# Pack_Supervisor_97x127mm_Rev_B.net
KiCad netlist of a schematic drawn in EAGLE
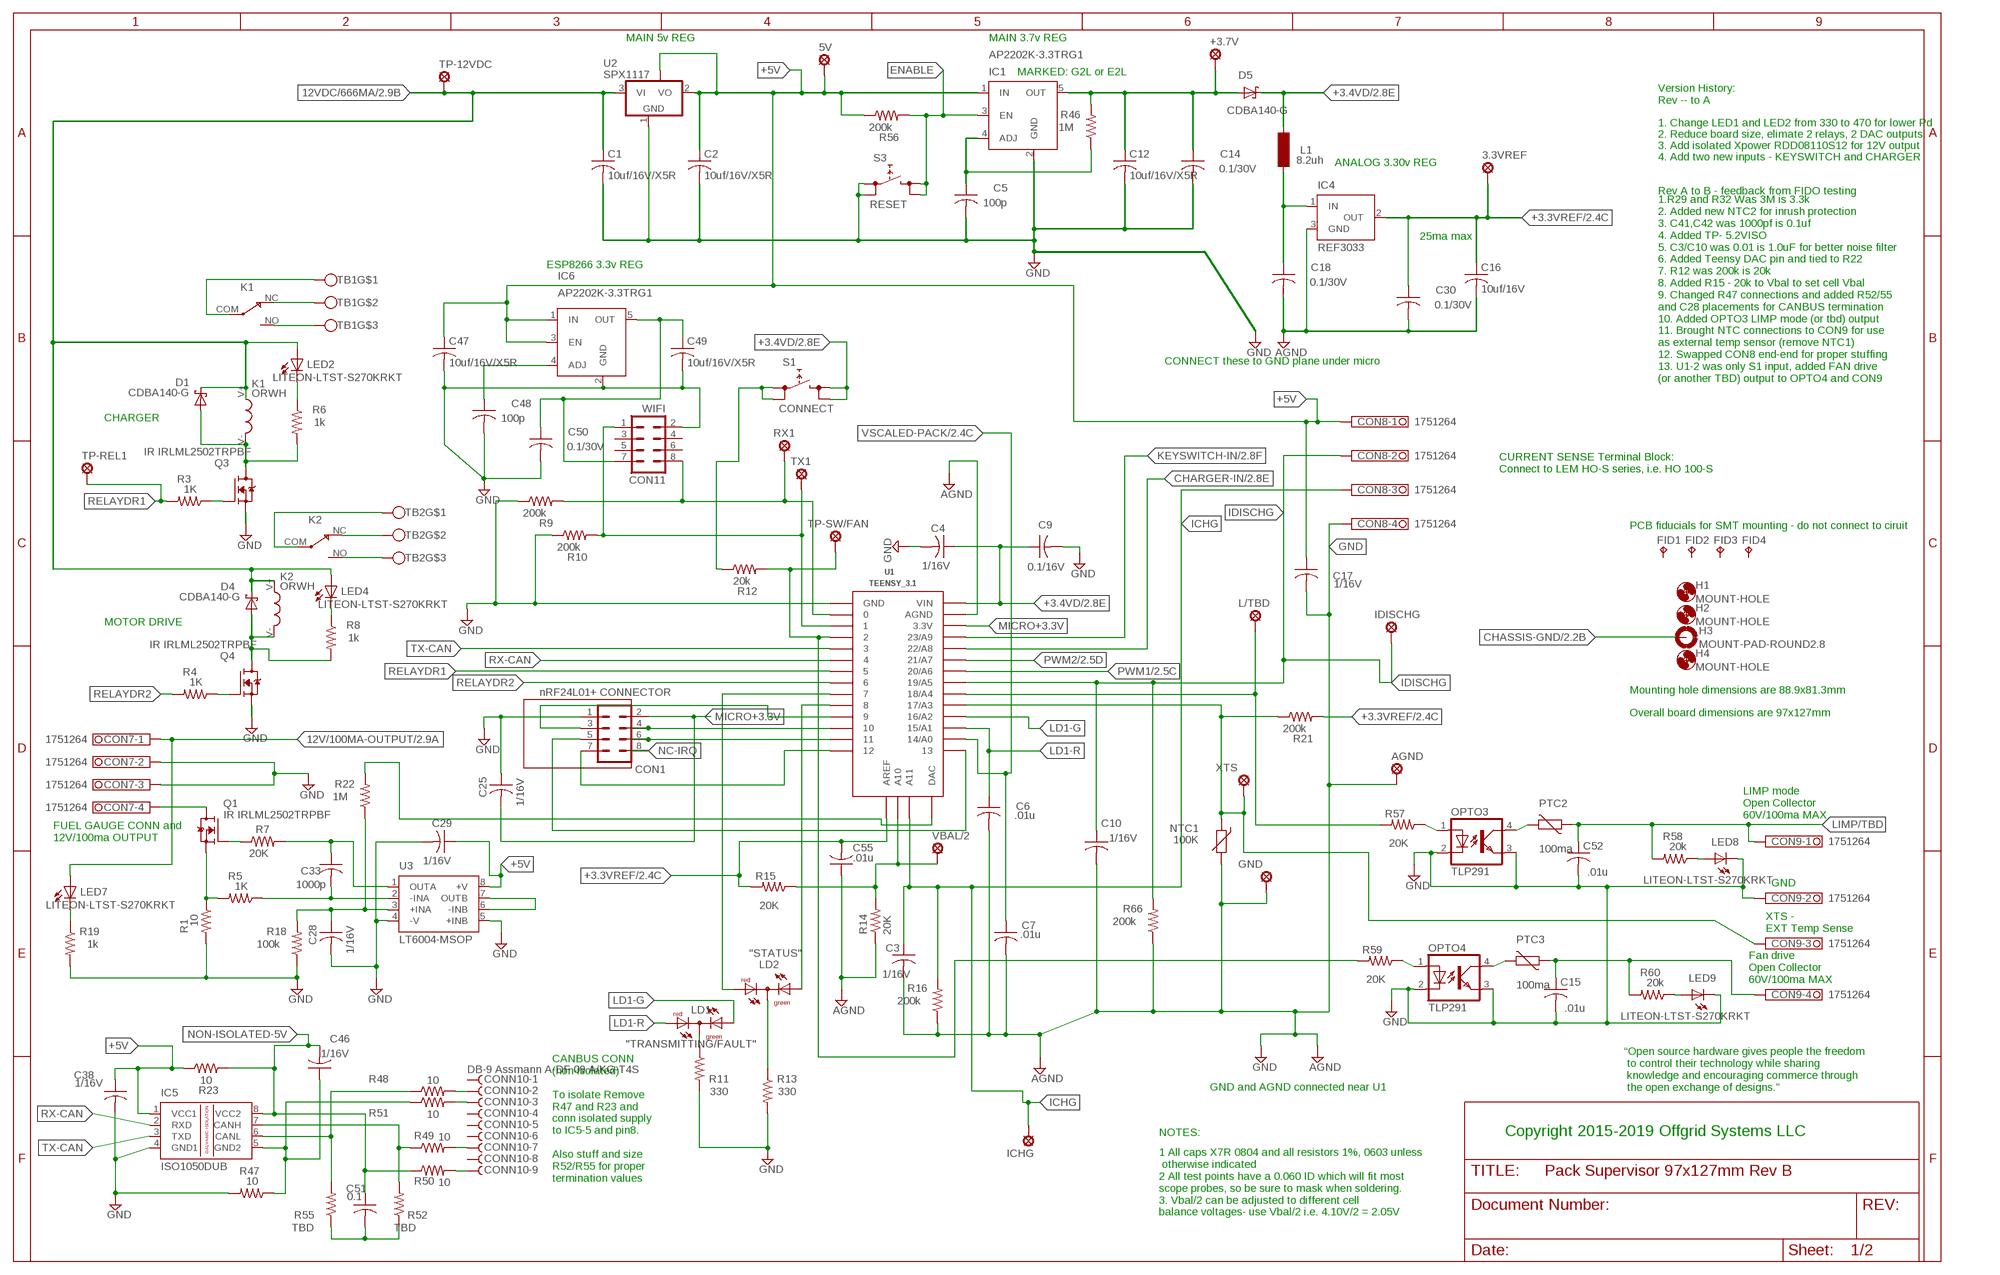
[diagram p0: schematic, sheet 1]
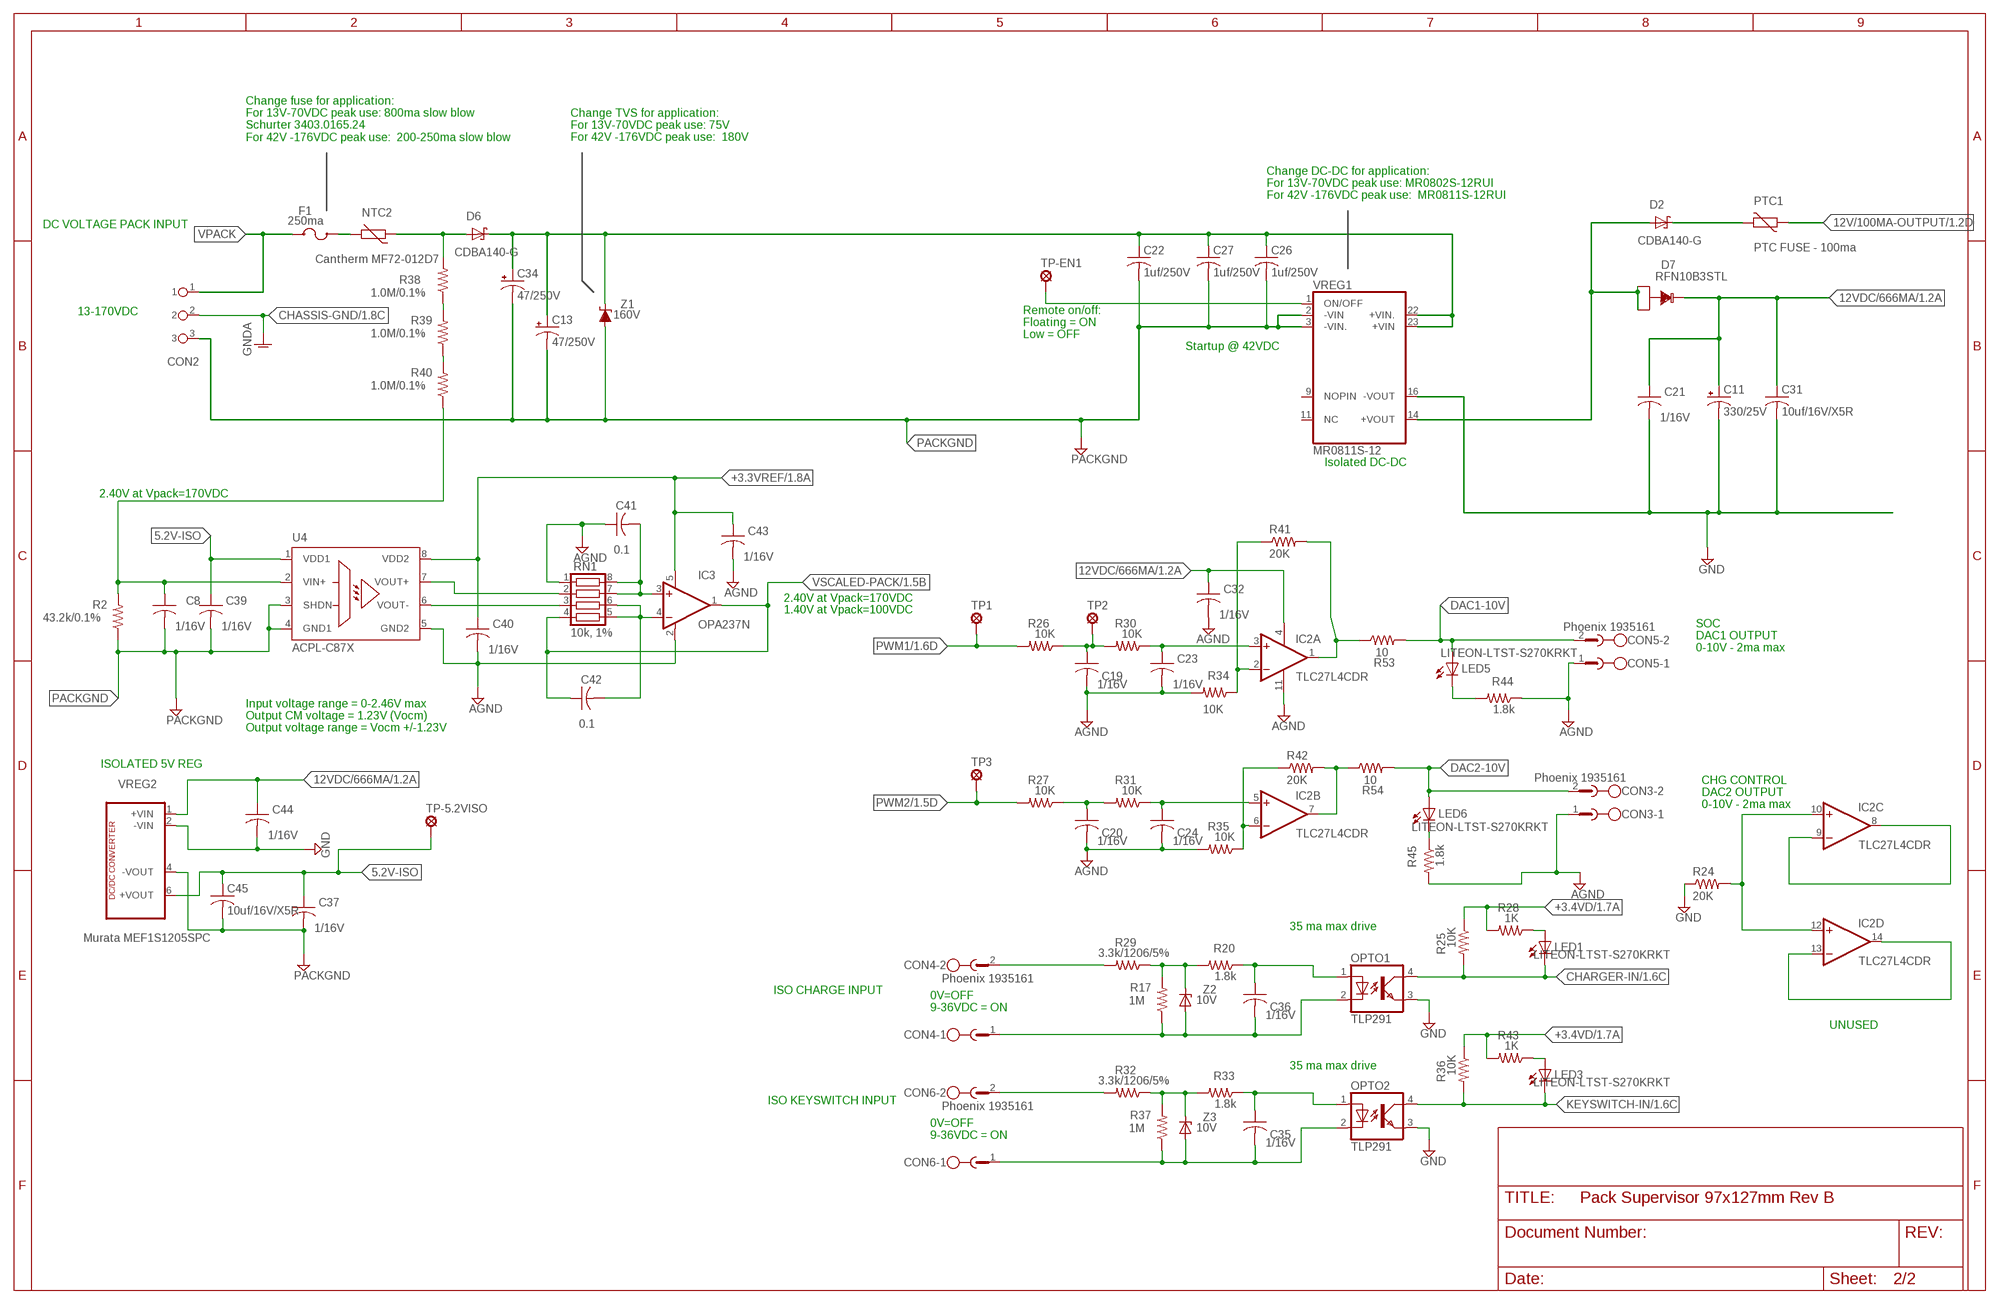
[diagram p1: schematic, sheet 2]

(export (version "E")
  (design (tool "Eeschema 10.0.6"))
  (components
    (comp (ref "+3.7V")
      (value "LSP10")
      (footprint "eagle-import:LSP10")
      (libsource (lib "eagle-import") (part "LSP10"))
    )
    (comp (ref "3.3VREF")
      (value "LSP10")
      (footprint "eagle-import:LSP10")
      (libsource (lib "eagle-import") (part "LSP10"))
    )
    (comp (ref "5V")
      (value "LSP10")
      (footprint "eagle-import:LSP10")
      (libsource (lib "eagle-import") (part "LSP10"))
    )
    (comp (ref "AGND")
      (value "LSP10")
      (footprint "eagle-import:LSP10")
      (libsource (lib "eagle-import") (part "LSP10"))
    )
    (comp (ref "C1")
      (value "10uf/16V/X5R")
      (footprint "eagle-import:C0805K")
      (fields (field (name "MPN") "Murata GRM21BR61C106ME15L"))
      (libsource (lib "eagle-import") (part "C-USC0805K"))
    )
    (comp (ref "C2")
      (value "10uf/16V/X5R")
      (footprint "eagle-import:C0805K")
      (fields (field (name "MPN") "Murata GRM21BR61C106ME15L"))
      (libsource (lib "eagle-import") (part "C-USC0805K"))
    )
    (comp (ref "C3")
      (value "1/16V")
      (footprint "eagle-import:TIMS_INDUCTOR_C0805")
      (fields (field (name "MPN") "Kemet C0805C103K5RACTU"))
      (libsource (lib "eagle-import") (part "TIMS_INDUCTOR_C-USC0805"))
    )
    (comp (ref "C4")
      (value "1/16V")
      (footprint "eagle-import:TIMS_INDUCTOR_C0805")
      (fields (field (name "MPN") "Kemet C0805C105K4RACTU"))
      (libsource (lib "eagle-import") (part "TIMS_INDUCTOR_C-USC0805"))
    )
    (comp (ref "C5")
      (value "100p")
      (footprint "eagle-import:TIMS_INDUCTOR_C0805")
      (fields (field (name "MPN") "Kemet C0805C104K5RACTU"))
      (libsource (lib "eagle-import") (part "TIMS_INDUCTOR_C-USC0805"))
    )
    (comp (ref "C6")
      (value ".01u")
      (footprint "eagle-import:TIMS_INDUCTOR_C0805")
      (fields (field (name "MPN") "Kemet C0805C103K5RACTU"))
      (libsource (lib "eagle-import") (part "TIMS_INDUCTOR_C-USC0805"))
    )
    (comp (ref "C7")
      (value ".01u")
      (footprint "eagle-import:TIMS_INDUCTOR_C0805")
      (fields (field (name "MPN") "Kemet C0805C103K5RACTU"))
      (libsource (lib "eagle-import") (part "TIMS_INDUCTOR_C-USC0805"))
    )
    (comp (ref "C9")
      (value "0.1/16V")
      (footprint "eagle-import:TIMS_INDUCTOR_C0805")
      (fields (field (name "MPN") "Kemet C0805C104K5RACTU"))
      (libsource (lib "eagle-import") (part "TIMS_INDUCTOR_C-USC0805"))
    )
    (comp (ref "C10")
      (value "1/16V")
      (footprint "eagle-import:TIMS_INDUCTOR_C0805")
      (fields (field (name "MPN") "Kemet C0805C103K5RACTU"))
      (libsource (lib "eagle-import") (part "TIMS_INDUCTOR_C-USC0805"))
    )
    (comp (ref "C12")
      (value "10uf/16V/X5R")
      (footprint "eagle-import:C0805K")
      (fields (field (name "MPN") "Murata GRM21BR61C106ME15L"))
      (libsource (lib "eagle-import") (part "C-USC0805K"))
    )
    (comp (ref "C14")
      (value "0.1/30V")
      (footprint "eagle-import:TIMS_INDUCTOR_C0805")
      (fields (field (name "MPN") "Kemet C0805C104K5RACTU"))
      (libsource (lib "eagle-import") (part "TIMS_INDUCTOR_C-USC0805"))
    )
    (comp (ref "C15")
      (value ".01u")
      (footprint "eagle-import:TIMS_INDUCTOR_C0805")
      (fields (field (name "MPN") "Kemet C0805C103K5RACTU"))
      (libsource (lib "eagle-import") (part "TIMS_INDUCTOR_C-USC0805"))
    )
    (comp (ref "C16")
      (value "10uf/16V")
      (footprint "eagle-import:C0805K")
      (fields (field (name "MPN") "Murata GRM21BR61A476ME15L"))
      (libsource (lib "eagle-import") (part "C-USC0805K"))
    )
    (comp (ref "C17")
      (value "1/16V")
      (footprint "eagle-import:TIMS_INDUCTOR_C0805")
      (fields (field (name "MPN") "Kemet C0805C105K4RACTU"))
      (libsource (lib "eagle-import") (part "TIMS_INDUCTOR_C-USC0805"))
    )
    (comp (ref "C18")
      (value "0.1/30V")
      (footprint "eagle-import:TIMS_INDUCTOR_C0805")
      (fields (field (name "MPN") "Kemet C0805C104K5RACTU"))
      (libsource (lib "eagle-import") (part "TIMS_INDUCTOR_C-USC0805"))
    )
    (comp (ref "C25")
      (value "1/16V")
      (footprint "eagle-import:TIMS_INDUCTOR_C0805")
      (fields (field (name "MPN") "Kemet C0805C105K4RACTU"))
      (libsource (lib "eagle-import") (part "TIMS_INDUCTOR_C-USC0805"))
    )
    (comp (ref "C28")
      (value "1/16V")
      (footprint "eagle-import:TIMS_INDUCTOR_C0805")
      (fields (field (name "MPN") "Kemet C0805C105K4RACTU"))
      (libsource (lib "eagle-import") (part "TIMS_INDUCTOR_C-USC0805"))
    )
    (comp (ref "C29")
      (value "1/16V")
      (footprint "eagle-import:TIMS_INDUCTOR_C0805")
      (fields (field (name "MPN") "Kemet C0805C105K4RACTU"))
      (libsource (lib "eagle-import") (part "TIMS_INDUCTOR_C-USC0805"))
    )
    (comp (ref "C30")
      (value "0.1/30V")
      (footprint "eagle-import:TIMS_INDUCTOR_C0805")
      (fields (field (name "MPN") "Kemet C0805C104K5RACTU"))
      (libsource (lib "eagle-import") (part "TIMS_INDUCTOR_C-USC0805"))
    )
    (comp (ref "C33")
      (value "1000p")
      (footprint "eagle-import:TIMS_INDUCTOR_C0805")
      (fields (field (name "MPN") "Kemet C0805C105K4RACTU"))
      (libsource (lib "eagle-import") (part "TIMS_INDUCTOR_C-USC0805"))
    )
    (comp (ref "C38")
      (value "1/16V")
      (footprint "eagle-import:TIMS_INDUCTOR_C0805")
      (fields (field (name "MPN") "Kemet C0805C105K4RACTU"))
      (libsource (lib "eagle-import") (part "TIMS_INDUCTOR_C-USC0805"))
    )
    (comp (ref "C46")
      (value "1/16V")
      (footprint "eagle-import:TIMS_INDUCTOR_C0805")
      (fields (field (name "MPN") "Kemet C0805C105K4RACTU"))
      (libsource (lib "eagle-import") (part "TIMS_INDUCTOR_C-USC0805"))
    )
    (comp (ref "C47")
      (value "10uf/16V/X5R")
      (footprint "eagle-import:C0805K")
      (fields (field (name "MPN") "Murata GRM21BR61C106ME15L"))
      (libsource (lib "eagle-import") (part "C-USC0805K"))
    )
    (comp (ref "C48")
      (value "100p")
      (footprint "eagle-import:TIMS_INDUCTOR_C0805")
      (fields (field (name "MPN") "Kemet C0805C104K5RACTU"))
      (libsource (lib "eagle-import") (part "TIMS_INDUCTOR_C-USC0805"))
    )
    (comp (ref "C49")
      (value "10uf/16V/X5R")
      (footprint "eagle-import:C0805K")
      (fields (field (name "MPN") "Murata GRM21BR61C106ME15L"))
      (libsource (lib "eagle-import") (part "C-USC0805K"))
    )
    (comp (ref "C50")
      (value "0.1/30V")
      (footprint "eagle-import:TIMS_INDUCTOR_C0805")
      (fields (field (name "MPN") "Kemet C0805C104K5RACTU"))
      (libsource (lib "eagle-import") (part "TIMS_INDUCTOR_C-USC0805"))
    )
    (comp (ref "C51")
      (value "0.1")
      (footprint "eagle-import:TIMS_INDUCTOR_C0805")
      (fields (field (name "MPN") "Kemet C0805C105K4RACTU"))
      (libsource (lib "eagle-import") (part "TIMS_INDUCTOR_C-USC0805"))
    )
    (comp (ref "C52")
      (value ".01u")
      (footprint "eagle-import:TIMS_INDUCTOR_C0805")
      (fields (field (name "MPN") "Kemet C0805C103K5RACTU"))
      (libsource (lib "eagle-import") (part "TIMS_INDUCTOR_C-USC0805"))
    )
    (comp (ref "C55")
      (value ".01u")
      (footprint "eagle-import:C0805")
      (fields (field (name "MPN") "Welwyn PCF0603R-3K01BT1"))
      (libsource (lib "eagle-import") (part "C-USC0805"))
    )
    (comp (ref "CON1")
      (value "nRF24L01+ CONNECTOR")
      (footprint "eagle-import:NRF24L01")
      (libsource (lib "eagle-import") (part "NRF24L01"))
    )
    (comp (ref "CON7")
      (value "1751264")
      (footprint "eagle-import:1751264")
      (libsource (lib "eagle-import") (part "1751264"))
    )
    (comp (ref "CON8")
      (value "1751264")
      (footprint "eagle-import:1751264")
      (libsource (lib "eagle-import") (part "1751264"))
    )
    (comp (ref "CON9")
      (value "1751264")
      (footprint "eagle-import:1751264")
      (libsource (lib "eagle-import") (part "1751264"))
    )
    (comp (ref "CON11")
      (value "WIFI")
      (footprint "eagle-import:MA04-2")
      (fields (field (name "MPN") "Sullins PPPC042LFBN-RC"))
      (libsource (lib "eagle-import") (part "MA04-2"))
    )
    (comp (ref "CONN10")
      (value "DB-9 Assmann A-DF 09 A/KG-T4S")
      (footprint "eagle-import:H5M09RA")
      (fields
        (field (name "100PCPRICE") ".563")
        (field (name "10PCPRICE") ".735")
        (field (name "MPN") "ASSMANN A-DS 09 A/KG-T4S")
      )
      (libsource (lib "eagle-import") (part "D-SUB9-H5M09RA"))
    )
    (comp (ref "D1")
      (value "CDBA140-G")
      (footprint "eagle-import:DO214AC")
      (fields (field (name "MPN") "comchip CDBA140-G"))
      (libsource (lib "eagle-import") (part "CDBA140-G"))
    )
    (comp (ref "D4")
      (value "CDBA140-G")
      (footprint "eagle-import:DO214AC")
      (fields (field (name "MPN") "comchip CDBA140-G"))
      (libsource (lib "eagle-import") (part "CDBA140-G"))
    )
    (comp (ref "D5")
      (value "CDBA140-G")
      (footprint "eagle-import:DO214AC")
      (fields (field (name "MPN") "comchip CDBA140-G"))
      (libsource (lib "eagle-import") (part "CDBA140-G"))
    )
    (comp (ref "FID1")
      (value "FIDUCIALTP10R")
      (footprint "eagle-import:TP10R")
      (libsource (lib "eagle-import") (part "FIDUCIALTP10R"))
    )
    (comp (ref "FID2")
      (value "FIDUCIALTP10R")
      (footprint "eagle-import:TP10R")
      (libsource (lib "eagle-import") (part "FIDUCIALTP10R"))
    )
    (comp (ref "FID3")
      (value "FIDUCIALTP10R")
      (footprint "eagle-import:TP10R")
      (libsource (lib "eagle-import") (part "FIDUCIALTP10R"))
    )
    (comp (ref "FID4")
      (value "FIDUCIALTP10R")
      (footprint "eagle-import:TP10R")
      (libsource (lib "eagle-import") (part "FIDUCIALTP10R"))
    )
    (comp (ref "GND")
      (value "LSP10")
      (footprint "eagle-import:LSP10")
      (libsource (lib "eagle-import") (part "LSP10"))
    )
    (comp (ref "H1")
      (value "MOUNT-HOLE")
      (footprint "eagle-import:2,6")
      (fields (field (name "MPN") "Keystone 9056"))
      (libsource (lib "eagle-import") (part "MOUNT-HOLE"))
    )
    (comp (ref "H2")
      (value "MOUNT-HOLE")
      (footprint "eagle-import:2,6")
      (libsource (lib "eagle-import") (part "MOUNT-HOLE"))
    )
    (comp (ref "H3")
      (value "MOUNT-PAD-ROUND2.8")
      (footprint "eagle-import:2,8-PAD")
      (libsource (lib "eagle-import") (part "MOUNT-PAD-ROUND2.8"))
    )
    (comp (ref "H4")
      (value "MOUNT-HOLE")
      (footprint "eagle-import:2,6")
      (libsource (lib "eagle-import") (part "MOUNT-HOLE"))
    )
    (comp (ref "IC1")
      (value "AP2202K-3.3TRG1")
      (footprint "eagle-import:SOT23-5")
      (fields
        (field (name "MF") "ALTERA CORPORATION")
        (field (name "MPN") "MIC5219BM5 TR")
        (field (name "MF_1") "Diodes INc")
        (field (name "MPN_1") "Diodes AP2202K-3.3TRG1")
      )
      (libsource (lib "eagle-import") (part "MIC5205"))
    )
    (comp (ref "IC4")
      (value "REF3033")
      (footprint "eagle-import:SOT23")
      (fields
        (field (name "MF") "MAXIM")
        (field (name "MPN") "MAX6520EUR-T")
        (field (name "MPN_1") "TI REF3033AIDBZR")
      )
      (libsource (lib "eagle-import") (part "MAX6520"))
    )
    (comp (ref "IC5")
      (value "ISO1050DUB")
      (footprint "eagle-import:DUB-R-PDSO-G8")
      (fields (field (name "MPN") "ISO1050DUBR") (field (name "MPN_1") "TI ISO1050DUBR"))
      (libsource (lib "eagle-import") (part "ISO1050DUB"))
    )
    (comp (ref "IC6")
      (value "AP2202K-3.3TRG1")
      (footprint "eagle-import:SOT23-5")
      (fields
        (field (name "MF") "ALTERA CORPORATION")
        (field (name "MPN") "MIC5219BM5 TR")
        (field (name "MF_1") "Diodes INc")
        (field (name "MPN_1") "Diodes AP2202K-3.3TRG1")
      )
      (libsource (lib "eagle-import") (part "MIC5205"))
    )
    (comp (ref "ICHG")
      (value "LSP10")
      (footprint "eagle-import:LSP10")
      (libsource (lib "eagle-import") (part "LSP10"))
    )
    (comp (ref "IDISCHG")
      (value "LSP10")
      (footprint "eagle-import:LSP10")
      (libsource (lib "eagle-import") (part "LSP10"))
    )
    (comp (ref "K1")
      (value "ORWH")
      (footprint "eagle-import:ORWH")
      (fields
        (field (name "MPN") "TE 1461069-5")
        (field (name "100PCPRICE") ".653")
        (field (name "1KPRICE") ".604")
      )
      (libsource (lib "eagle-import") (part "ORWH"))
    )
    (comp (ref "K2")
      (value "ORWH")
      (footprint "eagle-import:ORWH")
      (fields
        (field (name "MPN") "TE 1461069-5")
        (field (name "100PCPRICE") ".653")
        (field (name "1KPRICE") ".604")
      )
      (libsource (lib "eagle-import") (part "ORWH"))
    )
    (comp (ref "L/TBD")
      (value "LSP10")
      (footprint "eagle-import:LSP10")
      (libsource (lib "eagle-import") (part "LSP10"))
    )
    (comp (ref "L1")
      (value "8.2uh")
      (footprint "eagle-import:SM-1206")
      (fields (field (name "MPN") "Abracon AIML-1206-8R2K-T"))
      (libsource (lib "eagle-import") (part "SM-1206"))
    )
    (comp (ref "LD1")
      (value "\"TRANSMITTING/FAULT\"")
      (footprint "eagle-import:DUOLED-C-5MM")
      (fields (field (name "MPN") "Kingbright WP59EGC"))
      (libsource (lib "eagle-import") (part "DUOLED-RG-C"))
    )
    (comp (ref "LD2")
      (value "\"STATUS\"")
      (footprint "eagle-import:DUOLED-C-5MM")
      (fields (field (name "MPN") "Kingbright WP59EGC"))
      (libsource (lib "eagle-import") (part "DUOLED-RG-C"))
    )
    (comp (ref "LED2")
      (value "LITEON-LTST-S270KRKT")
      (footprint "eagle-import:LITEON-LTST-S270KRKT")
      (fields (field (name "MPN") "LiteOn LTST-S270KSKT "))
      (libsource (lib "eagle-import") (part "LITEON-LTST-S270KRKT"))
    )
    (comp (ref "LED4")
      (value "LITEON-LTST-S270KRKT")
      (footprint "eagle-import:LITEON-LTST-S270KRKT")
      (fields (field (name "MPN") "LiteOn LTST-S270KSKT "))
      (libsource (lib "eagle-import") (part "LITEON-LTST-S270KRKT"))
    )
    (comp (ref "LED7")
      (value "LITEON-LTST-S270KRKT")
      (footprint "eagle-import:LITEON-LTST-S270KRKT")
      (fields (field (name "MPN") "LiteOn LTST-S270KSKT "))
      (libsource (lib "eagle-import") (part "LITEON-LTST-S270KRKT"))
    )
    (comp (ref "LED8")
      (value "LITEON-LTST-S270KRKT")
      (footprint "eagle-import:LITEON-LTST-S270KRKT")
      (fields (field (name "MPN") "LiteOn LTST-S270KSKT "))
      (libsource (lib "eagle-import") (part "LITEON-LTST-S270KRKT"))
    )
    (comp (ref "LED9")
      (value "LITEON-LTST-S270KRKT")
      (footprint "eagle-import:LITEON-LTST-S270KRKT")
      (fields (field (name "MPN") "LiteOn LTST-S270KSKT "))
      (libsource (lib "eagle-import") (part "LITEON-LTST-S270KRKT"))
    )
    (comp (ref "NTC1")
      (value "100K")
      (footprint "eagle-import:0603")
      (fields (field (name "MPN") "MURATA NCP18WF104J03RB"))
      (libsource (lib "eagle-import") (part "NTC-MURATA-NCP18WF104J03RB"))
    )
    (comp (ref "OPTO3")
      (value "TLP291")
      (footprint "eagle-import:MINI-FLAT-4")
      (libsource (lib "eagle-import") (part "TLP283"))
    )
    (comp (ref "OPTO4")
      (value "TLP291")
      (footprint "eagle-import:MINI-FLAT-4")
      (libsource (lib "eagle-import") (part "TLP283"))
    )
    (comp (ref "PTC2")
      (value "100ma")
      (footprint "eagle-import:CT_CN0603")
      (fields (field (name "MPN") "Bel Fuse 0ZCM0010FF2G"))
      (libsource (lib "eagle-import") (part "VARISTORCN0603"))
    )
    (comp (ref "PTC3")
      (value "100ma")
      (footprint "eagle-import:CT_CN0603")
      (fields (field (name "MPN") "Bel Fuse 0ZCM0010FF2G"))
      (libsource (lib "eagle-import") (part "VARISTORCN0603"))
    )
    (comp (ref "Q1")
      (value "IRLML2502TRPBF")
      (footprint "eagle-import:SOT23")
      (fields (field (name "MPN") "IR IRLML2502TRPBF"))
      (libsource (lib "eagle-import") (part "IRLML2060TRPBF"))
    )
    (comp (ref "Q3")
      (value "IRLML2502TRPBF")
      (footprint "eagle-import:SOT23")
      (fields (field (name "MPN") "IR IRLML2502TRPBF"))
      (libsource (lib "eagle-import") (part "IRLML2060TRPBF"))
    )
    (comp (ref "Q4")
      (value "IRLML2502TRPBF")
      (footprint "eagle-import:SOT23")
      (fields (field (name "MPN") "IR IRLML2502TRPBF"))
      (libsource (lib "eagle-import") (part "IRLML2060TRPBF"))
    )
    (comp (ref "R1")
      (value "10")
      (footprint "eagle-import:R0603")
      (fields (field (name "MPN") "Bourns CR0603-FX-10R0ELF"))
      (libsource (lib "eagle-import") (part "rcl_R-US_R0603"))
    )
    (comp (ref "R3")
      (value "1K")
      (footprint "eagle-import:R0603")
      (fields (field (name "MPN") "Bourns CR0603-FX-1001ELF"))
      (libsource (lib "eagle-import") (part "rcl_R-US_R0603"))
    )
    (comp (ref "R4")
      (value "1K")
      (footprint "eagle-import:R0603")
      (fields (field (name "MPN") "Bourns CR0603-FX-1001ELF"))
      (libsource (lib "eagle-import") (part "rcl_R-US_R0603"))
    )
    (comp (ref "R5")
      (value "1K")
      (footprint "eagle-import:R0603")
      (fields (field (name "MPN") "Bourns CR0603-FX-1001ELF"))
      (libsource (lib "eagle-import") (part "rcl_R-US_R0603"))
    )
    (comp (ref "R6")
      (value "1k")
      (footprint "eagle-import:R0603")
      (fields (field (name "MPN") "Bourns CR0603-FX-3300ELF"))
      (libsource (lib "eagle-import") (part "rcl_R-US_R0603"))
    )
    (comp (ref "R7")
      (value "20K")
      (footprint "eagle-import:R0603")
      (fields (field (name "MPN") "Bourns CR0603-FX-2002ELF"))
      (libsource (lib "eagle-import") (part "rcl_R-US_R0603"))
    )
    (comp (ref "R8")
      (value "1k")
      (footprint "eagle-import:R0603")
      (fields (field (name "MPN") "Bourns CR0603-FX-3300ELF"))
      (libsource (lib "eagle-import") (part "rcl_R-US_R0603"))
    )
    (comp (ref "R9")
      (value "200k")
      (footprint "eagle-import:R0603")
      (fields (field (name "MPN") "Bourns CR0603-FX-2003ELF"))
      (libsource (lib "eagle-import") (part "rcl_R-US_R0603"))
    )
    (comp (ref "R10")
      (value "200k")
      (footprint "eagle-import:R0603")
      (fields (field (name "MPN") "Bourns CR0603-FX-2003ELF"))
      (libsource (lib "eagle-import") (part "rcl_R-US_R0603"))
    )
    (comp (ref "R11")
      (value "330")
      (footprint "eagle-import:R0603")
      (fields (field (name "MPN") "Bourns CR0603-FX-3300ELF"))
      (libsource (lib "eagle-import") (part "rcl_R-US_R0603"))
    )
    (comp (ref "R12")
      (value "20k")
      (footprint "eagle-import:R0603")
      (fields (field (name "MPN") "Bourns CR0603-FX-2003ELF"))
      (libsource (lib "eagle-import") (part "rcl_R-US_R0603"))
    )
    (comp (ref "R13")
      (value "330")
      (footprint "eagle-import:R0603")
      (fields (field (name "MPN") "Bourns CR0603-FX-3300ELF"))
      (libsource (lib "eagle-import") (part "rcl_R-US_R0603"))
    )
    (comp (ref "R14")
      (value "20K")
      (footprint "eagle-import:R0603")
      (fields (field (name "MPN") "Bourns CR0603-FX-2002ELF"))
      (libsource (lib "eagle-import") (part "rcl_R-US_R0603"))
    )
    (comp (ref "R15")
      (value "20K")
      (footprint "eagle-import:R0603")
      (fields (field (name "MPN") "Bourns CR0603-FX-2002ELF"))
      (libsource (lib "eagle-import") (part "rcl_R-US_R0603"))
    )
    (comp (ref "R16")
      (value "200k")
      (footprint "eagle-import:R0603")
      (fields (field (name "MPN") "Bourns CR0603-FX-2003ELF"))
      (libsource (lib "eagle-import") (part "rcl_R-US_R0603"))
    )
    (comp (ref "R18")
      (value "100k")
      (footprint "eagle-import:R0603")
      (fields (field (name "MPN") "Bourns CR0603-FX-1003ELF"))
      (libsource (lib "eagle-import") (part "rcl_R-US_R0603"))
    )
    (comp (ref "R19")
      (value "1k")
      (footprint "eagle-import:R0603")
      (fields (field (name "MPN") "Bourns CR0603-FX-3300ELF"))
      (libsource (lib "eagle-import") (part "rcl_R-US_R0603"))
    )
    (comp (ref "R21")
      (value "200k")
      (footprint "eagle-import:R0603")
      (fields (field (name "MPN") "Bourns CR0603-FX-2003ELF"))
      (libsource (lib "eagle-import") (part "rcl_R-US_R0603"))
    )
    (comp (ref "R22")
      (value "1M")
      (footprint "eagle-import:R0603")
      (fields (field (name "MPN") "Bourns CR0603-FX-1004ELF "))
      (libsource (lib "eagle-import") (part "rcl_R-US_R0603"))
    )
    (comp (ref "R23")
      (value "10")
      (footprint "eagle-import:R0603")
      (fields (field (name "MPN") "Bourns CR0603-FX-10R0ELF"))
      (libsource (lib "eagle-import") (part "rcl_R-US_R0603"))
    )
    (comp (ref "R46")
      (value "1M")
      (footprint "eagle-import:R0603")
      (fields (field (name "MPN") "Bourns CR0603-FX-1004ELF "))
      (libsource (lib "eagle-import") (part "rcl_R-US_R0603"))
    )
    (comp (ref "R47")
      (value "10")
      (footprint "eagle-import:R0603")
      (fields (field (name "MPN") "Bourns CR0603-FX-10R0ELF"))
      (libsource (lib "eagle-import") (part "rcl_R-US_R0603"))
    )
    (comp (ref "R48")
      (value "10")
      (footprint "eagle-import:R0603")
      (fields (field (name "MPN") "Bourns CR0603-FX-10R0ELF"))
      (libsource (lib "eagle-import") (part "rcl_R-US_R0603"))
    )
    (comp (ref "R49")
      (value "10")
      (footprint "eagle-import:R0603")
      (fields (field (name "MPN") "Bourns CR0603-FX-10R0ELF"))
      (libsource (lib "eagle-import") (part "rcl_R-US_R0603"))
    )
    (comp (ref "R50")
      (value "10")
      (footprint "eagle-import:R0603")
      (fields (field (name "MPN") "Bourns CR0603-FX-10R0ELF"))
      (libsource (lib "eagle-import") (part "rcl_R-US_R0603"))
    )
    (comp (ref "R51")
      (value "10")
      (footprint "eagle-import:R0603")
      (fields (field (name "MPN") "Bourns CR0603-FX-10R0ELF"))
      (libsource (lib "eagle-import") (part "rcl_R-US_R0603"))
    )
    (comp (ref "R52")
      (value "TBD")
      (footprint "eagle-import:0207_5V")
      (libsource (lib "eagle-import") (part "R-US_0207/5V"))
    )
    (comp (ref "R55")
      (value "TBD")
      (footprint "eagle-import:0207_5V")
      (libsource (lib "eagle-import") (part "R-US_0207/5V"))
    )
    (comp (ref "R56")
      (value "200k")
      (footprint "eagle-import:R0603")
      (fields (field (name "MPN") "Bourns CR0603-FX-2003ELF"))
      (libsource (lib "eagle-import") (part "rcl_R-US_R0603"))
    )
    (comp (ref "R57")
      (value "20K")
      (footprint "eagle-import:R0603")
      (fields (field (name "MPN") "Bourns CR0603-FX-2002ELF"))
      (libsource (lib "eagle-import") (part "rcl_R-US_R0603"))
    )
    (comp (ref "R58")
      (value "20k")
      (footprint "eagle-import:R0603")
      (fields (field (name "MPN") "Bourns CR0603-FX-1001ELF"))
      (libsource (lib "eagle-import") (part "rcl_R-US_R0603"))
    )
    (comp (ref "R59")
      (value "20K")
      (footprint "eagle-import:R0603")
      (fields (field (name "MPN") "Bourns CR0603-FX-2002ELF"))
      (libsource (lib "eagle-import") (part "rcl_R-US_R0603"))
    )
    (comp (ref "R60")
      (value "20k")
      (footprint "eagle-import:R0603")
      (fields (field (name "MPN") "Bourns CR0603-FX-1001ELF"))
      (libsource (lib "eagle-import") (part "rcl_R-US_R0603"))
    )
    (comp (ref "R66")
      (value "200k")
      (footprint "eagle-import:R0603")
      (fields (field (name "MPN") "Bourns CR0603-FX-2003ELF"))
      (libsource (lib "eagle-import") (part "rcl_R-US_R0603"))
    )
    (comp (ref "RX1")
      (value "LSP10")
      (footprint "eagle-import:LSP10")
      (libsource (lib "eagle-import") (part "LSP10"))
    )
    (comp (ref "S1")
      (value "CONNECT")
      (footprint "eagle-import:PTS645")
      (fields (field (name "MPN") "C&k PTS645SM43SMTR92 LFS"))
      (libsource (lib "eagle-import") (part "PTS645"))
    )
    (comp (ref "S3")
      (value "RESET")
      (footprint "eagle-import:PTS645")
      (fields (field (name "MPN") "C&k PTS645SM43SMTR92 LFS"))
      (libsource (lib "eagle-import") (part "PTS645"))
    )
    (comp (ref "TB1")
      (value "TE-5-1437652-4")
      (footprint "eagle-import:TE-5-1437652-4")
      (fields
        (field (name "MPN") "TE 5-1437652-4")
        (field (name "100PCPRICE") "1.16")
        (field (name "1KPRICE") ".84")
      )
      (libsource (lib "eagle-import") (part "TE-5-1437652-4"))
    )
    (comp (ref "TB2")
      (value "TE-5-1437652-4")
      (footprint "eagle-import:TE-5-1437652-4")
      (fields
        (field (name "100PCPRICE") "1.16")
        (field (name "1KPRICE") ".84")
        (field (name "MPN") "TE 5-1437652-4")
      )
      (libsource (lib "eagle-import") (part "TE-5-1437652-4"))
    )
    (comp (ref "TP-12VDC")
      (value "LSP10")
      (footprint "eagle-import:LSP10")
      (libsource (lib "eagle-import") (part "LSP10"))
    )
    (comp (ref "TP-REL1")
      (value "LSP10")
      (footprint "eagle-import:LSP10")
      (libsource (lib "eagle-import") (part "LSP10"))
    )
    (comp (ref "TP-SW/FAN")
      (value "LSP10")
      (footprint "eagle-import:LSP10")
      (libsource (lib "eagle-import") (part "LSP10"))
    )
    (comp (ref "TX1")
      (value "LSP10")
      (footprint "eagle-import:LSP10")
      (libsource (lib "eagle-import") (part "LSP10"))
    )
    (comp (ref "U1")
      (value "TEENSY_3.1")
      (footprint "eagle-import:TEENSY_3.0-DIP+ANALOG+DAC")
      (fields (field (name "MPN") "OshPark Teensy 3.1"))
      (libsource (lib "eagle-import") (part "TEENSY_3.0-DIP+ANALOG"))
    )
    (comp (ref "U2")
      (value "SPX1117")
      (footprint "eagle-import:SOT223")
      (fields (field (name "MPN") "Exar SPX1117M3-L-5-0/TR"))
      (libsource (lib "eagle-import") (part "SPX1117"))
    )
    (comp (ref "U3")
      (value "LT6004-MSOP")
      (footprint "eagle-import:LT6004-MSOP")
      (fields (field (name "MPN") "LTC LT6004CMS8"))
      (libsource (lib "eagle-import") (part "LT6004-MSOP"))
    )
    (comp (ref "VBAL/2")
      (value "LSP10")
      (footprint "eagle-import:LSP10")
      (libsource (lib "eagle-import") (part "LSP10"))
    )
    (comp (ref "XTS")
      (value "LSP10")
      (footprint "eagle-import:LSP10")
      (libsource (lib "eagle-import") (part "LSP10"))
    )
    (comp (ref "C8")
      (value "1/16V")
      (footprint "eagle-import:TIMS_INDUCTOR_C0805")
      (fields (field (name "MPN") "Kemet C0805C105K4RACTU"))
      (libsource (lib "eagle-import") (part "TIMS_INDUCTOR_C-USC0805"))
    )
    (comp (ref "C11")
      (value "330/25V")
      (footprint "eagle-import:E5-10,5")
      (libsource (lib "eagle-import") (part "CPOL-USE5-10.5"))
    )
    (comp (ref "C13")
      (value "47/250V")
      (footprint "eagle-import:E5-13")
      (fields (field (name "MPN") "PANASONIC ECA-2EM470"))
      (libsource (lib "eagle-import") (part "CPOL-USE5-13"))
    )
    (comp (ref "C19")
      (value "1/16V")
      (footprint "eagle-import:TIMS_INDUCTOR_C0805")
      (fields (field (name "MPN") "Kemet C0805C105K4RACTU"))
      (libsource (lib "eagle-import") (part "TIMS_INDUCTOR_C-USC0805"))
    )
    (comp (ref "C20")
      (value "1/16V")
      (footprint "eagle-import:TIMS_INDUCTOR_C0805")
      (fields (field (name "MPN") "Kemet C0805C105K4RACTU"))
      (libsource (lib "eagle-import") (part "TIMS_INDUCTOR_C-USC0805"))
    )
    (comp (ref "C21")
      (value "1/16V")
      (footprint "eagle-import:TIMS_INDUCTOR_C0805")
      (fields (field (name "MPN") "Kemet C0805C105K4RACTU"))
      (libsource (lib "eagle-import") (part "TIMS_INDUCTOR_C-USC0805"))
    )
    (comp (ref "C22")
      (value "1uf/250V")
      (footprint "eagle-import:RCL_C050-030X075")
      (libsource (lib "eagle-import") (part "RCL_C-US050-030X075"))
    )
    (comp (ref "C23")
      (value "1/16V")
      (footprint "eagle-import:TIMS_INDUCTOR_C0805")
      (fields (field (name "MPN") "Kemet C0805C105K4RACTU"))
      (libsource (lib "eagle-import") (part "TIMS_INDUCTOR_C-USC0805"))
    )
    (comp (ref "C24")
      (value "1/16V")
      (footprint "eagle-import:TIMS_INDUCTOR_C0805")
      (fields (field (name "MPN") "Kemet C0805C105K4RACTU"))
      (libsource (lib "eagle-import") (part "TIMS_INDUCTOR_C-USC0805"))
    )
    (comp (ref "C26")
      (value "1uf/250V")
      (footprint "eagle-import:RCL_C050-030X075")
      (libsource (lib "eagle-import") (part "RCL_C-US050-030X075"))
    )
    (comp (ref "C27")
      (value "1uf/250V")
      (footprint "eagle-import:RCL_C050-030X075")
      (libsource (lib "eagle-import") (part "RCL_C-US050-030X075"))
    )
    (comp (ref "C31")
      (value "10uf/16V/X5R")
      (footprint "eagle-import:C0805K")
      (fields (field (name "MPN") "Murata GRM21BR61C106ME15L"))
      (libsource (lib "eagle-import") (part "C-USC0805K"))
    )
    (comp (ref "C32")
      (value "1/16V")
      (footprint "eagle-import:TIMS_INDUCTOR_C0805")
      (fields (field (name "MPN") "Kemet C0805C105K4RACTU"))
      (libsource (lib "eagle-import") (part "TIMS_INDUCTOR_C-USC0805"))
    )
    (comp (ref "C34")
      (value "47/250V")
      (footprint "eagle-import:E5-13")
      (fields (field (name "MPN") "PANASONIC ECA-2EM470"))
      (libsource (lib "eagle-import") (part "CPOL-USE5-13"))
    )
    (comp (ref "C35")
      (value "1/16V")
      (footprint "eagle-import:TIMS_INDUCTOR_C0805")
      (fields (field (name "MPN") "Kemet C0805C105K4RACTU"))
      (libsource (lib "eagle-import") (part "TIMS_INDUCTOR_C-USC0805"))
    )
    (comp (ref "C36")
      (value "1/16V")
      (footprint "eagle-import:TIMS_INDUCTOR_C0805")
      (fields (field (name "MPN") "Kemet C0805C105K4RACTU"))
      (libsource (lib "eagle-import") (part "TIMS_INDUCTOR_C-USC0805"))
    )
    (comp (ref "C37")
      (value "1/16V")
      (footprint "eagle-import:TIMS_INDUCTOR_C0805")
      (fields (field (name "MPN") "Kemet C0805C105K4RACTU"))
      (libsource (lib "eagle-import") (part "TIMS_INDUCTOR_C-USC0805"))
    )
    (comp (ref "C39")
      (value "1/16V")
      (footprint "eagle-import:TIMS_INDUCTOR_C0805")
      (fields (field (name "MPN") "Kemet C0805C105K4RACTU"))
      (libsource (lib "eagle-import") (part "TIMS_INDUCTOR_C-USC0805"))
    )
    (comp (ref "C40")
      (value "1/16V")
      (footprint "eagle-import:TIMS_INDUCTOR_C0805")
      (fields (field (name "MPN") "Kemet C0805C105K4RACTU"))
      (libsource (lib "eagle-import") (part "TIMS_INDUCTOR_C-USC0805"))
    )
    (comp (ref "C41")
      (value "0.1")
      (footprint "eagle-import:TIMS_INDUCTOR_C0805")
      (fields (field (name "MPN") "Kemet C0805C105K4RACTU"))
      (libsource (lib "eagle-import") (part "TIMS_INDUCTOR_C-USC0805"))
    )
    (comp (ref "C42")
      (value "0.1")
      (footprint "eagle-import:TIMS_INDUCTOR_C0805")
      (fields (field (name "MPN") "Kemet C0805C105K4RACTU"))
      (libsource (lib "eagle-import") (part "TIMS_INDUCTOR_C-USC0805"))
    )
    (comp (ref "C43")
      (value "1/16V")
      (footprint "eagle-import:TIMS_INDUCTOR_C0805")
      (fields (field (name "MPN") "Kemet C0805C105K4RACTU"))
      (libsource (lib "eagle-import") (part "TIMS_INDUCTOR_C-USC0805"))
    )
    (comp (ref "C44")
      (value "1/16V")
      (footprint "eagle-import:TIMS_INDUCTOR_C0805")
      (fields (field (name "MPN") "Kemet C0805C105K4RACTU"))
      (libsource (lib "eagle-import") (part "TIMS_INDUCTOR_C-USC0805"))
    )
    (comp (ref "C45")
      (value "10uf/16V/X5R")
      (footprint "eagle-import:C0805K")
      (fields (field (name "MPN") "Murata GRM21BR61C106ME15L"))
      (libsource (lib "eagle-import") (part "C-USC0805K"))
    )
    (comp (ref "CON2")
      (value "TYCO-796739-3")
      (footprint "eagle-import:TYCO-796739-3")
      (libsource (lib "eagle-import") (part "TYCO-796739-3"))
    )
    (comp (ref "CON3")
      (value "Phoenix 1935161")
      (footprint "eagle-import:MSTBV2")
      (fields
        (field (name "MPN") "Phoenix 1935161")
        (field (name "100PCPRICE") ".327")
        (field (name "10PCPRICE") ".352")
      )
      (libsource (lib "eagle-import") (part "MSTBV2"))
    )
    (comp (ref "CON4")
      (value "Phoenix 1935161")
      (footprint "eagle-import:MSTBV2")
      (fields
        (field (name "MPN") "Phoenix 1935161")
        (field (name "100PCPRICE") ".327")
        (field (name "10PCPRICE") ".352")
      )
      (libsource (lib "eagle-import") (part "MSTBV2"))
    )
    (comp (ref "CON5")
      (value "Phoenix 1935161")
      (footprint "eagle-import:MSTBV2")
      (fields
        (field (name "MPN") "Phoenix 1935161")
        (field (name "100PCPRICE") ".327")
        (field (name "10PCPRICE") ".352")
      )
      (libsource (lib "eagle-import") (part "MSTBV2"))
    )
    (comp (ref "CON6")
      (value "Phoenix 1935161")
      (footprint "eagle-import:MSTBV2")
      (fields
        (field (name "100PCPRICE") ".327")
        (field (name "10PCPRICE") ".352")
        (field (name "MPN") "Phoenix 1935161")
      )
      (libsource (lib "eagle-import") (part "MSTBV2"))
    )
    (comp (ref "D2")
      (value "CDBA140-G")
      (footprint "eagle-import:DO214AC")
      (fields (field (name "MPN") "comchip CDBA140-G"))
      (libsource (lib "eagle-import") (part "CDBA140-G"))
    )
    (comp (ref "D6")
      (value "CDBA140-G")
      (footprint "eagle-import:DO214AC")
      (fields (field (name "MPN") "comchip CDBA140-G"))
      (libsource (lib "eagle-import") (part "CDBA140-G"))
    )
    (comp (ref "D7")
      (value "RFN10B3STL")
      (footprint "eagle-import:TO252-FATPADS")
      (fields (field (name "MPN") "ROHM RFN10B3STL"))
      (libsource (lib "eagle-import") (part "RFN10B3STL"))
    )
    (comp (ref "F1")
      (value "250ma")
      (footprint "eagle-import:SCHURTER-UMT250")
      (fields (field (name "MPN") "Schurter 3403.0159.24"))
      (libsource (lib "eagle-import") (part "SCHURTER-UMT250"))
    )
    (comp (ref "IC2")
      (value "TLC27L4CDR")
      (footprint "eagle-import:SO14")
      (fields
        (field (name "100PCPRICE") ".581")
        (field (name "1KPRICE") ".39")
        (field (name "MPN") "TI TLC27L4CDR")
      )
      (libsource (lib "eagle-import") (part "OPA4UA134"))
    )
    (comp (ref "IC3")
      (value "OPA237N")
      (footprint "eagle-import:SOT23-5")
      (fields (field (name "MPN") "TI OPA237NA/3K"))
      (libsource (lib "eagle-import") (part "OPA237N"))
    )
    (comp (ref "LED1")
      (value "LITEON-LTST-S270KRKT")
      (footprint "eagle-import:LITEON-LTST-S270KRKT")
      (fields (field (name "MPN") "LiteOn LTST-S270KSKT "))
      (libsource (lib "eagle-import") (part "LITEON-LTST-S270KRKT"))
    )
    (comp (ref "LED3")
      (value "LITEON-LTST-S270KRKT")
      (footprint "eagle-import:LITEON-LTST-S270KRKT")
      (fields (field (name "MPN") "LiteOn LTST-S270KSKT "))
      (libsource (lib "eagle-import") (part "LITEON-LTST-S270KRKT"))
    )
    (comp (ref "LED5")
      (value "LITEON-LTST-S270KRKT")
      (footprint "eagle-import:LITEON-LTST-S270KRKT")
      (fields (field (name "MPN") "LiteOn LTST-S270KSKT "))
      (libsource (lib "eagle-import") (part "LITEON-LTST-S270KRKT"))
    )
    (comp (ref "LED6")
      (value "LITEON-LTST-S270KRKT")
      (footprint "eagle-import:LITEON-LTST-S270KRKT")
      (fields (field (name "MPN") "LiteOn LTST-S270KSKT "))
      (libsource (lib "eagle-import") (part "LITEON-LTST-S270KRKT"))
    )
    (comp (ref "NTC2")
      (value "Cantherm MF72-012D7")
      (footprint "eagle-import:D7-PACKAGE")
      (libsource (lib "eagle-import") (part "NTC-GLASS"))
    )
    (comp (ref "OPTO1")
      (value "TLP291")
      (footprint "eagle-import:MINI-FLAT-4")
      (libsource (lib "eagle-import") (part "TLP283"))
    )
    (comp (ref "OPTO2")
      (value "TLP291")
      (footprint "eagle-import:MINI-FLAT-4")
      (libsource (lib "eagle-import") (part "TLP283"))
    )
    (comp (ref "PTC1")
      (value "PTC FUSE - 100ma")
      (footprint "eagle-import:CT_CN0603")
      (fields (field (name "MPN") "Bel Fuse 0ZCM0010FF2G"))
      (libsource (lib "eagle-import") (part "VARISTORCN0603"))
    )
    (comp (ref "R2")
      (value "43.2k/0.1%")
      (footprint "eagle-import:R0603")
      (fields (field (name "MPN") "Panasonic ERA-3AEB4322V "))
      (libsource (lib "eagle-import") (part "rcl_R-US_R0603"))
    )
    (comp (ref "R17")
      (value "1M")
      (footprint "eagle-import:R0603")
      (fields (field (name "MPN") "Bourns CR0603-FX-1004ELF "))
      (libsource (lib "eagle-import") (part "rcl_R-US_R0603"))
    )
    (comp (ref "R20")
      (value "1.8k")
      (footprint "eagle-import:R0603")
      (fields (field (name "MPN") "Bourns CR0603-FX-1821ELF"))
      (libsource (lib "eagle-import") (part "rcl_R-US_R0603"))
    )
    (comp (ref "R24")
      (value "20K")
      (footprint "eagle-import:R0603")
      (fields (field (name "MPN") "Bourns CR0603-FX-2002ELF"))
      (libsource (lib "eagle-import") (part "rcl_R-US_R0603"))
    )
    (comp (ref "R25")
      (value "10K")
      (footprint "eagle-import:R0603")
      (fields (field (name "MPN") "Bourns CR0603-FX-1002ELF"))
      (libsource (lib "eagle-import") (part "rcl_R-US_R0603"))
    )
    (comp (ref "R26")
      (value "10K")
      (footprint "eagle-import:R0603")
      (fields (field (name "MPN") "Bourns CR0603-FX-1002ELF"))
      (libsource (lib "eagle-import") (part "rcl_R-US_R0603"))
    )
    (comp (ref "R27")
      (value "10K")
      (footprint "eagle-import:R0603")
      (fields (field (name "MPN") "Bourns CR0603-FX-1002ELF"))
      (libsource (lib "eagle-import") (part "rcl_R-US_R0603"))
    )
    (comp (ref "R28")
      (value "1K")
      (footprint "eagle-import:R0603")
      (fields (field (name "MPN") "Bourns CR0603-FX-1001ELF"))
      (libsource (lib "eagle-import") (part "rcl_R-US_R0603"))
    )
    (comp (ref "R29")
      (value "3.3k/1206/5%")
      (footprint "eagle-import:R1206")
      (fields (field (name "MPN") "Panasonic ERJ-8GEYJ305V"))
      (libsource (lib "eagle-import") (part "rcl_R-US_R1206"))
    )
    (comp (ref "R30")
      (value "10K")
      (footprint "eagle-import:R0603")
      (fields (field (name "MPN") "Bourns CR0603-FX-1002ELF"))
      (libsource (lib "eagle-import") (part "rcl_R-US_R0603"))
    )
    (comp (ref "R31")
      (value "10K")
      (footprint "eagle-import:R0603")
      (fields (field (name "MPN") "Bourns CR0603-FX-1002ELF"))
      (libsource (lib "eagle-import") (part "rcl_R-US_R0603"))
    )
    (comp (ref "R32")
      (value "3.3k/1206/5%")
      (footprint "eagle-import:R1206")
      (fields (field (name "MPN") "Panasonic ERJ-8GEYJ305V"))
      (libsource (lib "eagle-import") (part "rcl_R-US_R1206"))
    )
    (comp (ref "R33")
      (value "1.8k")
      (footprint "eagle-import:R0603")
      (fields (field (name "MPN") "Bourns CR0603-FX-1821ELF"))
      (libsource (lib "eagle-import") (part "rcl_R-US_R0603"))
    )
    (comp (ref "R34")
      (value "10K")
      (footprint "eagle-import:R0603")
      (fields (field (name "MPN") "Bourns CR0603-FX-1002ELF"))
      (libsource (lib "eagle-import") (part "rcl_R-US_R0603"))
    )
    (comp (ref "R35")
      (value "10K")
      (footprint "eagle-import:R0603")
      (fields (field (name "MPN") "Bourns CR0603-FX-1002ELF"))
      (libsource (lib "eagle-import") (part "rcl_R-US_R0603"))
    )
    (comp (ref "R36")
      (value "10K")
      (footprint "eagle-import:R0603")
      (fields (field (name "MPN") "Bourns CR0603-FX-1002ELF"))
      (libsource (lib "eagle-import") (part "rcl_R-US_R0603"))
    )
    (comp (ref "R37")
      (value "1M")
      (footprint "eagle-import:R0603")
      (fields (field (name "MPN") "Bourns CR0603-FX-1004ELF "))
      (libsource (lib "eagle-import") (part "rcl_R-US_R0603"))
    )
    (comp (ref "R38")
      (value "1.0M/0.1%")
      (footprint "eagle-import:R0805")
      (fields (field (name "MPN") "Panasonic ERA-6AEB105V"))
      (libsource (lib "eagle-import") (part "rcl_R-US_R0805"))
    )
    (comp (ref "R39")
      (value "1.0M/0.1%")
      (footprint "eagle-import:R0805")
      (fields (field (name "MPN") "Panasonic ERA-6AEB105V"))
      (libsource (lib "eagle-import") (part "rcl_R-US_R0805"))
    )
    (comp (ref "R40")
      (value "1.0M/0.1%")
      (footprint "eagle-import:R0805")
      (fields (field (name "MPN") "Panasonic ERA-6AEB105V"))
      (libsource (lib "eagle-import") (part "rcl_R-US_R0805"))
    )
    (comp (ref "R41")
      (value "20K")
      (footprint "eagle-import:R0603")
      (fields (field (name "MPN") "Bourns CR0603-FX-2002ELF"))
      (libsource (lib "eagle-import") (part "rcl_R-US_R0603"))
    )
    (comp (ref "R42")
      (value "20K")
      (footprint "eagle-import:R0603")
      (fields (field (name "MPN") "Bourns CR0603-FX-2002ELF"))
      (libsource (lib "eagle-import") (part "rcl_R-US_R0603"))
    )
    (comp (ref "R43")
      (value "1K")
      (footprint "eagle-import:R0603")
      (fields (field (name "MPN") "Bourns CR0603-FX-1001ELF"))
      (libsource (lib "eagle-import") (part "rcl_R-US_R0603"))
    )
    (comp (ref "R44")
      (value "1.8k")
      (footprint "eagle-import:R0603")
      (fields (field (name "MPN") "Bourns CR0603-FX-1821ELF"))
      (libsource (lib "eagle-import") (part "rcl_R-US_R0603"))
    )
    (comp (ref "R45")
      (value "1.8k")
      (footprint "eagle-import:R0603")
      (fields (field (name "MPN") "Bourns CR0603-FX-1821ELF"))
      (libsource (lib "eagle-import") (part "rcl_R-US_R0603"))
    )
    (comp (ref "R53")
      (value "10")
      (footprint "eagle-import:R0603")
      (fields (field (name "MPN") "Bourns CR0603-FX-10R0ELF"))
      (libsource (lib "eagle-import") (part "rcl_R-US_R0603"))
    )
    (comp (ref "R54")
      (value "10")
      (footprint "eagle-import:R0603")
      (fields (field (name "MPN") "Bourns CR0603-FX-10R0ELF"))
      (libsource (lib "eagle-import") (part "rcl_R-US_R0603"))
    )
    (comp (ref "RN1")
      (value "10k, 1%")
      (footprint "eagle-import:CTS742C083")
      (fields (field (name "MPN") "Yageo TC164-FR-0710KL"))
      (libsource (lib "eagle-import") (part "CTS742C083"))
    )
    (comp (ref "TP-5.2VISO")
      (value "LSP10")
      (footprint "eagle-import:LSP10")
      (libsource (lib "eagle-import") (part "LSP10"))
    )
    (comp (ref "TP-EN1")
      (value "LSP10")
      (footprint "eagle-import:LSP10")
      (libsource (lib "eagle-import") (part "LSP10"))
    )
    (comp (ref "TP1")
      (value "LSP10")
      (footprint "eagle-import:LSP10")
      (libsource (lib "eagle-import") (part "LSP10"))
    )
    (comp (ref "TP2")
      (value "LSP10")
      (footprint "eagle-import:LSP10")
      (libsource (lib "eagle-import") (part "LSP10"))
    )
    (comp (ref "TP3")
      (value "LSP10")
      (footprint "eagle-import:LSP10")
      (libsource (lib "eagle-import") (part "LSP10"))
    )
    (comp (ref "U4")
      (value "ACPL-C87X")
      (footprint "eagle-import:STRETCH-SO8")
      (fields (field (name "MPN") "Avago Broadcomm ACPL-C87B-000E"))
      (libsource (lib "eagle-import") (part "ACPL-C87X"))
    )
    (comp (ref "VREG1")
      (value "MR0811S-12")
      (footprint "eagle-import:MR0811S-12")
      (fields (field (name "MPN") "Micropower Direct MR0811S-12RUI"))
      (libsource (lib "eagle-import") (part "MR0811S-12"))
    )
    (comp (ref "VREG2")
      (value "Murata MEF1S1205SPC")
      (footprint "eagle-import:MURATA-MEF")
      (libsource (lib "eagle-import") (part "MURATA-MEF-ISODCDC"))
    )
    (comp (ref "Z1")
      (value "160V")
      (footprint "eagle-import:SMB")
      (fields (field (name "MPN") "ON SEMI 1SMB5954BT3G"))
      (libsource (lib "eagle-import") (part "ZENER-SMB"))
    )
    (comp (ref "Z2")
      (value "10V")
      (footprint "eagle-import:TIMS_DIODE_SOT23")
      (fields (field (name "MPN") "ON SEMI SZBZX84C10LT1G"))
      (libsource (lib "eagle-import") (part "TIMS_DIODE_ZENER-DIODESOT23"))
    )
    (comp (ref "Z3")
      (value "10V")
      (footprint "eagle-import:TIMS_DIODE_SOT23")
      (fields (field (name "MPN") "ON SEMI SZBZX84C10LT1G"))
      (libsource (lib "eagle-import") (part "TIMS_DIODE_ZENER-DIODESOT23"))
    )
  )
  (nets
    (net (code "1") (name "+3.3VREF") (class "Default")
      (node (ref "3.3VREF") (pin "MP") (pinfunction "MP_MP") (pintype "passive"))
      (node (ref "C16") (pin "1") (pinfunction "1_1") (pintype "passive"))
      (node (ref "C30") (pin "1") (pinfunction "1_1") (pintype "passive"))
      (node (ref "C40") (pin "1") (pinfunction "1_1") (pintype "passive"))
      (node (ref "C43") (pin "1") (pinfunction "1_1") (pintype "passive"))
      (node (ref "C55") (pin "2") (pinfunction "2_2") (pintype "passive"))
      (node (ref "IC3") (pin "5") (pinfunction "V+_5") (pintype "power_in"))
      (node (ref "IC4") (pin "2") (pinfunction "OUT_2") (pintype "output"))
      (node (ref "R15") (pin "2") (pinfunction "2_2") (pintype "passive"))
      (node (ref "R21") (pin "2") (pinfunction "2_2") (pintype "passive"))
      (node (ref "U1") (pin "AREF") (pinfunction "AREF_AREF") (pintype "power_in"))
      (node (ref "U4") (pin "8") (pinfunction "VDD2_8") (pintype "power_in"))
    )
    (net (code "2") (name "+3.4VD") (class "Default")
      (node (ref "C4") (pin "1") (pinfunction "1_1") (pintype "passive"))
      (node (ref "C9") (pin "1") (pinfunction "1_1") (pintype "passive"))
      (node (ref "D5") (pin "C") (pinfunction "C_C") (pintype "passive"))
      (node (ref "L1") (pin "2") (pinfunction "2_2") (pintype "passive"))
      (node (ref "R25") (pin "1") (pinfunction "1_1") (pintype "passive"))
      (node (ref "R28") (pin "2") (pinfunction "2_2") (pintype "passive"))
      (node (ref "R36") (pin "1") (pinfunction "1_1") (pintype "passive"))
      (node (ref "R43") (pin "2") (pinfunction "2_2") (pintype "passive"))
      (node (ref "S1") (pin "3") (pinfunction "3_3") (pintype "passive"))
      (node (ref "S1") (pin "4") (pinfunction "4_4") (pintype "passive"))
      (node (ref "U1") (pin "VIN") (pinfunction "VIN_VIN") (pintype "power_in"))
    )
    (net (code "3") (name "+5V") (class "Default")
      (node (ref "5V") (pin "MP") (pinfunction "MP_MP") (pintype "passive"))
      (node (ref "C17") (pin "1") (pinfunction "1_1") (pintype "passive"))
      (node (ref "C2") (pin "1") (pinfunction "1_1") (pintype "passive"))
      (node (ref "C29") (pin "1") (pinfunction "1_1") (pintype "passive"))
      (node (ref "C38") (pin "1") (pinfunction "1_1") (pintype "passive"))
      (node (ref "C47") (pin "1") (pinfunction "1_1") (pintype "passive"))
      (node (ref "CON8") (pin "1") (pinfunction "K_1") (pintype "passive"))
      (node (ref "IC1") (pin "1") (pinfunction "IN_1") (pintype "input"))
      (node (ref "IC5") (pin "1") (pinfunction "VCC1_1") (pintype "input"))
      (node (ref "IC6") (pin "1") (pinfunction "IN_1") (pintype "input"))
      (node (ref "IC6") (pin "3") (pinfunction "EN_3") (pintype "input"))
      (node (ref "R23") (pin "1") (pinfunction "1_1") (pintype "passive"))
      (node (ref "R56") (pin "1") (pinfunction "1_1") (pintype "passive"))
      (node (ref "U2") (pin "2") (pinfunction "VO_2") (pintype "passive"))
      (node (ref "U2") (pin "4") (pinfunction "TAB_4") (pintype "passive"))
      (node (ref "U3") (pin "8") (pinfunction "+V_8") (pintype "input"))
    )
    (net (code "4") (name "5.2V-ISO") (class "Default")
      (node (ref "C37") (pin "1") (pinfunction "1_1") (pintype "passive"))
      (node (ref "C39") (pin "1") (pinfunction "1_1") (pintype "passive"))
      (node (ref "C45") (pin "1") (pinfunction "1_1") (pintype "passive"))
      (node (ref "TP-5.2VISO") (pin "MP") (pinfunction "MP_MP") (pintype "passive"))
      (node (ref "U4") (pin "1") (pinfunction "VDD1_1") (pintype "power_in"))
      (node (ref "VREG2") (pin "6") (pinfunction "+VOUT_6") (pintype "passive"))
    )
    (net (code "5") (name "12VDC{slash}666MA") (class "Default")
      (node (ref "C1") (pin "1") (pinfunction "1_1") (pintype "passive"))
      (node (ref "C11") (pin "+") (pinfunction "+_+") (pintype "passive"))
      (node (ref "C21") (pin "1") (pinfunction "1_1") (pintype "passive"))
      (node (ref "C31") (pin "1") (pinfunction "1_1") (pintype "passive"))
      (node (ref "C32") (pin "1") (pinfunction "1_1") (pintype "passive"))
      (node (ref "C44") (pin "1") (pinfunction "1_1") (pintype "passive"))
      (node (ref "D1") (pin "C") (pinfunction "C_C") (pintype "passive"))
      (node (ref "D4") (pin "C") (pinfunction "C_C") (pintype "passive"))
      (node (ref "D7") (pin "DRAIN") (pinfunction "CATHODE_DRAIN") (pintype "passive"))
      (node (ref "IC2") (pin "4") (pinfunction "V+_4") (pintype "power_in"))
      (node (ref "K1") (pin "V+") (pinfunction "V+_V+") (pintype "passive"))
      (node (ref "K2") (pin "V+") (pinfunction "V+_V+") (pintype "passive"))
      (node (ref "LED2") (pin "ANODE") (pinfunction "A_ANODE") (pintype "passive"))
      (node (ref "LED4") (pin "ANODE") (pinfunction "A_ANODE") (pintype "passive"))
      (node (ref "TP-12VDC") (pin "MP") (pinfunction "MP_MP") (pintype "passive"))
      (node (ref "U2") (pin "3") (pinfunction "VI_3") (pintype "input"))
      (node (ref "VREG2") (pin "1") (pinfunction "+VIN_1") (pintype "passive"))
    )
    (net (code "6") (name "12V{slash}100MA-OUTPUT") (class "Default")
      (node (ref "CON7") (pin "1") (pinfunction "K_1") (pintype "passive"))
      (node (ref "LED7") (pin "ANODE") (pinfunction "A_ANODE") (pintype "passive"))
      (node (ref "PTC1") (pin "1") (pinfunction "1_1") (pintype "passive"))
    )
    (net (code "7") (name "CHARGER-IN") (class "Default")
      (node (ref "LED1") (pin "CATHODE") (pinfunction "C_CATHODE") (pintype "passive"))
      (node (ref "OPTO1") (pin "4") (pinfunction "COL_4") (pintype "passive"))
      (node (ref "R25") (pin "2") (pinfunction "2_2") (pintype "passive"))
      (node (ref "U1") (pin "22/A8") (pinfunction "22/A8_22/A8") (pintype "bidirectional"))
    )
    (net (code "8") (name "CHASSIS-GND") (class "Default")
      (node (ref "CON2") (pin "2") (pinfunction "2_2") (pintype "passive"))
      (node (ref "H3") (pin "B2,8") (pinfunction "MOUNT_B2,8") (pintype "passive"))
    )
    (net (code "9") (name "DAC1-10V") (class "Default")
      (node (ref "CON5") (pin "2") (pinfunction "1_2") (pintype "passive"))
      (node (ref "LED5") (pin "ANODE") (pinfunction "A_ANODE") (pintype "passive"))
      (node (ref "R53") (pin "2") (pinfunction "2_2") (pintype "passive"))
    )
    (net (code "10") (name "DAC2-10V") (class "Default")
      (node (ref "CON3") (pin "2") (pinfunction "1_2") (pintype "passive"))
      (node (ref "LED6") (pin "ANODE") (pinfunction "A_ANODE") (pintype "passive"))
      (node (ref "R54") (pin "2") (pinfunction "2_2") (pintype "passive"))
    )
    (net (code "11") (name "ENABLE") (class "Default")
      (node (ref "IC1") (pin "3") (pinfunction "EN_3") (pintype "input"))
      (node (ref "R56") (pin "2") (pinfunction "2_2") (pintype "passive"))
      (node (ref "S3") (pin "3") (pinfunction "3_3") (pintype "passive"))
      (node (ref "S3") (pin "4") (pinfunction "4_4") (pintype "passive"))
    )
    (net (code "12") (name "GND") (class "Default")
      (node (ref "AGND") (pin "MP") (pinfunction "MP_MP") (pintype "passive"))
      (node (ref "C1") (pin "2") (pinfunction "2_2") (pintype "passive"))
      (node (ref "C10") (pin "2") (pinfunction "2_2") (pintype "passive"))
      (node (ref "C11") (pin "-") (pinfunction "-_-") (pintype "passive"))
      (node (ref "C12") (pin "2") (pinfunction "2_2") (pintype "passive"))
      (node (ref "C14") (pin "2") (pinfunction "2_2") (pintype "passive"))
      (node (ref "C15") (pin "2") (pinfunction "2_2") (pintype "passive"))
      (node (ref "C16") (pin "2") (pinfunction "2_2") (pintype "passive"))
      (node (ref "C17") (pin "2") (pinfunction "2_2") (pintype "passive"))
      (node (ref "C18") (pin "2") (pinfunction "2_2") (pintype "passive"))
      (node (ref "C19") (pin "2") (pinfunction "2_2") (pintype "passive"))
      (node (ref "C2") (pin "2") (pinfunction "2_2") (pintype "passive"))
      (node (ref "C20") (pin "2") (pinfunction "2_2") (pintype "passive"))
      (node (ref "C21") (pin "2") (pinfunction "2_2") (pintype "passive"))
      (node (ref "C23") (pin "2") (pinfunction "2_2") (pintype "passive"))
      (node (ref "C24") (pin "2") (pinfunction "2_2") (pintype "passive"))
      (node (ref "C25") (pin "1") (pinfunction "1_1") (pintype "passive"))
      (node (ref "C28") (pin "2") (pinfunction "2_2") (pintype "passive"))
      (node (ref "C29") (pin "2") (pinfunction "2_2") (pintype "passive"))
      (node (ref "C3") (pin "2") (pinfunction "2_2") (pintype "passive"))
      (node (ref "C30") (pin "2") (pinfunction "2_2") (pintype "passive"))
      (node (ref "C31") (pin "2") (pinfunction "2_2") (pintype "passive"))
      (node (ref "C32") (pin "2") (pinfunction "2_2") (pintype "passive"))
      (node (ref "C38") (pin "2") (pinfunction "2_2") (pintype "passive"))
      (node (ref "C4") (pin "2") (pinfunction "2_2") (pintype "passive"))
      (node (ref "C40") (pin "2") (pinfunction "2_2") (pintype "passive"))
      (node (ref "C41") (pin "1") (pinfunction "1_1") (pintype "passive"))
      (node (ref "C43") (pin "2") (pinfunction "2_2") (pintype "passive"))
      (node (ref "C44") (pin "2") (pinfunction "2_2") (pintype "passive"))
      (node (ref "C47") (pin "2") (pinfunction "2_2") (pintype "passive"))
      (node (ref "C48") (pin "2") (pinfunction "2_2") (pintype "passive"))
      (node (ref "C49") (pin "2") (pinfunction "2_2") (pintype "passive"))
      (node (ref "C5") (pin "2") (pinfunction "2_2") (pintype "passive"))
      (node (ref "C50") (pin "2") (pinfunction "2_2") (pintype "passive"))
      (node (ref "C52") (pin "2") (pinfunction "2_2") (pintype "passive"))
      (node (ref "C55") (pin "1") (pinfunction "1_1") (pintype "passive"))
      (node (ref "C6") (pin "2") (pinfunction "2_2") (pintype "passive"))
      (node (ref "C7") (pin "2") (pinfunction "2_2") (pintype "passive"))
      (node (ref "C9") (pin "2") (pinfunction "2_2") (pintype "passive"))
      (node (ref "CON1") (pin "1") (pinfunction "1_1") (pintype "passive"))
      (node (ref "CON11") (pin "2") (pinfunction "2_2") (pintype "passive"))
      (node (ref "CON3") (pin "1") (pinfunction "1_1") (pintype "passive"))
      (node (ref "CON5") (pin "1") (pinfunction "1_1") (pintype "passive"))
      (node (ref "CON7") (pin "2") (pinfunction "K_2") (pintype "passive"))
      (node (ref "CON7") (pin "3") (pinfunction "K_3") (pintype "passive"))
      (node (ref "CON8") (pin "4") (pinfunction "K_4") (pintype "passive"))
      (node (ref "CON9") (pin "2") (pinfunction "K_2") (pintype "passive"))
      (node (ref "GND") (pin "MP") (pinfunction "MP_MP") (pintype "passive"))
      (node (ref "IC1") (pin "2") (pinfunction "GND_2") (pintype "power_in"))
      (node (ref "IC2") (pin "11") (pinfunction "V-_11") (pintype "power_in"))
      (node (ref "IC3") (pin "2") (pinfunction "V-_2") (pintype "power_in"))
      (node (ref "IC4") (pin "3") (pinfunction "GND_3") (pintype "power_in"))
      (node (ref "IC5") (pin "4") (pinfunction "GND1_4") (pintype "input"))
      (node (ref "IC6") (pin "2") (pinfunction "GND_2") (pintype "power_in"))
      (node (ref "LED8") (pin "CATHODE") (pinfunction "C_CATHODE") (pintype "passive"))
      (node (ref "LED9") (pin "CATHODE") (pinfunction "C_CATHODE") (pintype "passive"))
      (node (ref "NTC1") (pin "2") (pinfunction "2_2") (pintype "passive"))
      (node (ref "OPTO1") (pin "3") (pinfunction "EMIT_3") (pintype "passive"))
      (node (ref "OPTO2") (pin "3") (pinfunction "EMIT_3") (pintype "passive"))
      (node (ref "OPTO3") (pin "2") (pinfunction "C_2") (pintype "passive"))
      (node (ref "OPTO3") (pin "3") (pinfunction "EMIT_3") (pintype "passive"))
      (node (ref "OPTO4") (pin "2") (pinfunction "C_2") (pintype "passive"))
      (node (ref "OPTO4") (pin "3") (pinfunction "EMIT_3") (pintype "passive"))
      (node (ref "Q3") (pin "2") (pinfunction "S_2") (pintype "passive"))
      (node (ref "Q4") (pin "2") (pinfunction "S_2") (pintype "passive"))
      (node (ref "R1") (pin "2") (pinfunction "2_2") (pintype "passive"))
      (node (ref "R10") (pin "1") (pinfunction "1_1") (pintype "passive"))
      (node (ref "R11") (pin "2") (pinfunction "2_2") (pintype "passive"))
      (node (ref "R13") (pin "2") (pinfunction "2_2") (pintype "passive"))
      (node (ref "R14") (pin "1") (pinfunction "1_1") (pintype "passive"))
      (node (ref "R16") (pin "1") (pinfunction "1_1") (pintype "passive"))
      (node (ref "R18") (pin "1") (pinfunction "1_1") (pintype "passive"))
      (node (ref "R19") (pin "2") (pinfunction "2_2") (pintype "passive"))
      (node (ref "R24") (pin "1") (pinfunction "1_1") (pintype "passive"))
      (node (ref "R34") (pin "2") (pinfunction "2_2") (pintype "passive"))
      (node (ref "R35") (pin "2") (pinfunction "2_2") (pintype "passive"))
      (node (ref "R44") (pin "1") (pinfunction "1_1") (pintype "passive"))
      (node (ref "R45") (pin "2") (pinfunction "2_2") (pintype "passive"))
      (node (ref "R47") (pin "2") (pinfunction "2_2") (pintype "passive"))
      (node (ref "R66") (pin "1") (pinfunction "1_1") (pintype "passive"))
      (node (ref "R9") (pin "1") (pinfunction "1_1") (pintype "passive"))
      (node (ref "RN1") (pin "1") (pinfunction "1_1") (pintype "passive"))
      (node (ref "S3") (pin "1") (pinfunction "1_1") (pintype "passive"))
      (node (ref "S3") (pin "2") (pinfunction "2_2") (pintype "passive"))
      (node (ref "U1") (pin "AGND") (pinfunction "AGND_AGND") (pintype "power_in"))
      (node (ref "U1") (pin "GND") (pinfunction "GND_GND") (pintype "power_in"))
      (node (ref "U2") (pin "1") (pinfunction "GND_1") (pintype "passive"))
      (node (ref "U3") (pin "4") (pinfunction "-V_4") (pintype "input"))
      (node (ref "U3") (pin "5") (pinfunction "+INB_5") (pintype "input"))
      (node (ref "U4") (pin "5") (pinfunction "GND2_5") (pintype "power_in"))
      (node (ref "VREG1") (pin "16") (pinfunction "-VOUT_16") (pintype "input"))
      (node (ref "VREG2") (pin "2") (pinfunction "-VIN_2") (pintype "passive"))
    )
    (net (code "13") (name "ICHG") (class "Default")
      (node (ref "C3") (pin "1") (pinfunction "1_1") (pintype "passive"))
      (node (ref "CON8") (pin "3") (pinfunction "K_3") (pintype "passive"))
      (node (ref "ICHG") (pin "MP") (pinfunction "MP_MP") (pintype "passive"))
      (node (ref "R16") (pin "2") (pinfunction "2_2") (pintype "passive"))
      (node (ref "U1") (pin "A11") (pinfunction "A11_A11") (pintype "input"))
    )
    (net (code "14") (name "IDISCHG") (class "Default")
      (node (ref "C10") (pin "1") (pinfunction "1_1") (pintype "passive"))
      (node (ref "CON8") (pin "2") (pinfunction "K_2") (pintype "passive"))
      (node (ref "IDISCHG") (pin "MP") (pinfunction "MP_MP") (pintype "passive"))
      (node (ref "R66") (pin "2") (pinfunction "2_2") (pintype "passive"))
      (node (ref "U1") (pin "19/A5") (pinfunction "19/A5_19/A5") (pintype "bidirectional"))
    )
    (net (code "15") (name "KEYSWITCH-IN") (class "Default")
      (node (ref "LED3") (pin "CATHODE") (pinfunction "C_CATHODE") (pintype "passive"))
      (node (ref "OPTO2") (pin "4") (pinfunction "COL_4") (pintype "passive"))
      (node (ref "R36") (pin "2") (pinfunction "2_2") (pintype "passive"))
      (node (ref "U1") (pin "23/A9") (pinfunction "23/A9_23/A9") (pintype "bidirectional"))
    )
    (net (code "16") (name "LD1-G") (class "Default")
      (node (ref "LD1") (pin "AX") (pinfunction "AG_AX") (pintype "passive"))
      (node (ref "U1") (pin "16/A2") (pinfunction "16/A2_16/A2") (pintype "bidirectional"))
    )
    (net (code "17") (name "LD1-R") (class "Default")
      (node (ref "C6") (pin "1") (pinfunction "1_1") (pintype "passive"))
      (node (ref "LD1") (pin "AR") (pinfunction "AR_AR") (pintype "passive"))
      (node (ref "U1") (pin "15/A1") (pinfunction "15/A1_15/A1") (pintype "bidirectional"))
    )
    (net (code "18") (name "LIMP{slash}TBD") (class "Default")
      (node (ref "C52") (pin "1") (pinfunction "1_1") (pintype "passive"))
      (node (ref "CON9") (pin "1") (pinfunction "K_1") (pintype "passive"))
      (node (ref "PTC2") (pin "1") (pinfunction "1_1") (pintype "passive"))
      (node (ref "R58") (pin "2") (pinfunction "2_2") (pintype "passive"))
    )
    (net (code "19") (name "MICRO+3.3V") (class "Default")
      (node (ref "C25") (pin "2") (pinfunction "2_2") (pintype "passive"))
      (node (ref "CON1") (pin "2") (pinfunction "2_2") (pintype "passive"))
      (node (ref "U1") (pin "3.3V") (pinfunction "3.3V_3.3V") (pintype "power_in"))
    )
    (net (code "20") (name "NC-IRQ") (class "Default")
      (node (ref "CON1") (pin "8") (pinfunction "8_8") (pintype "passive"))
    )
    (net (code "21") (name "NON-ISOLATED-5V") (class "Default")
      (node (ref "C46") (pin "2") (pinfunction "2_2") (pintype "passive"))
      (node (ref "C51") (pin "1") (pinfunction "1_1") (pintype "passive"))
      (node (ref "IC5") (pin "8") (pinfunction "VCC2_8") (pintype "input"))
      (node (ref "R23") (pin "2") (pinfunction "2_2") (pintype "passive"))
      (node (ref "R50") (pin "1") (pinfunction "1_1") (pintype "passive"))
    )
    (net (code "22") (name "Net-(C19-Pad1)") (class "Default")
      (node (ref "C19") (pin "1") (pinfunction "1_1") (pintype "passive"))
      (node (ref "R26") (pin "1") (pinfunction "1_1") (pintype "passive"))
      (node (ref "R30") (pin "2") (pinfunction "2_2") (pintype "passive"))
      (node (ref "TP2") (pin "MP") (pinfunction "MP_MP") (pintype "passive"))
    )
    (net (code "23") (name "Net-(C20-Pad1)") (class "Default")
      (node (ref "C20") (pin "1") (pinfunction "1_1") (pintype "passive"))
      (node (ref "R27") (pin "1") (pinfunction "1_1") (pintype "passive"))
      (node (ref "R31") (pin "2") (pinfunction "2_2") (pintype "passive"))
    )
    (net (code "24") (name "Net-(C51-Pad2)") (class "Default")
      (node (ref "C51") (pin "2") (pinfunction "2_2") (pintype "passive"))
      (node (ref "R52") (pin "1") (pinfunction "1_1") (pintype "passive"))
      (node (ref "R55") (pin "1") (pinfunction "1_1") (pintype "passive"))
    )
    (net (code "25") (name "Net-(CON1-Pad3)") (class "Default")
      (node (ref "CON1") (pin "3") (pinfunction "3_3") (pintype "passive"))
      (node (ref "U1") (pin "9") (pinfunction "9_9") (pintype "bidirectional"))
    )
    (net (code "26") (name "Net-(CON1-Pad4)") (class "Default")
      (node (ref "CON1") (pin "4") (pinfunction "4_4") (pintype "passive"))
      (node (ref "U1") (pin "10") (pinfunction "10_10") (pintype "bidirectional"))
    )
    (net (code "27") (name "Net-(CON1-Pad5)") (class "Default")
      (node (ref "CON1") (pin "5") (pinfunction "5_5") (pintype "passive"))
      (node (ref "U1") (pin "13") (pinfunction "13_13") (pintype "bidirectional"))
    )
    (net (code "28") (name "Net-(CON1-Pad6)") (class "Default")
      (node (ref "CON1") (pin "6") (pinfunction "6_6") (pintype "passive"))
      (node (ref "U1") (pin "11") (pinfunction "11_11") (pintype "bidirectional"))
    )
    (net (code "29") (name "Net-(CON1-Pad7)") (class "Default")
      (node (ref "CON1") (pin "7") (pinfunction "7_7") (pintype "passive"))
      (node (ref "U1") (pin "12") (pinfunction "12_12") (pintype "bidirectional"))
    )
    (net (code "30") (name "Net-(CON4B-1)") (class "Default")
      (node (ref "CON4") (pin "2") (pinfunction "1_2") (pintype "passive"))
      (node (ref "R29") (pin "2") (pinfunction "2_2") (pintype "passive"))
    )
    (net (code "31") (name "Net-(CON6B-1)") (class "Default")
      (node (ref "CON6") (pin "2") (pinfunction "1_2") (pintype "passive"))
      (node (ref "R32") (pin "2") (pinfunction "2_2") (pintype "passive"))
    )
    (net (code "32") (name "Net-(CON7D-K)") (class "Default")
      (node (ref "CON7") (pin "4") (pinfunction "K_4") (pintype "passive"))
      (node (ref "Q1") (pin "3") (pinfunction "D_3") (pintype "passive"))
    )
    (net (code "33") (name "Net-(CON9C-K)") (class "Default")
      (node (ref "CON9") (pin "3") (pinfunction "K_3") (pintype "passive"))
      (node (ref "NTC1") (pin "1") (pinfunction "1_1") (pintype "passive"))
      (node (ref "R21") (pin "1") (pinfunction "1_1") (pintype "passive"))
      (node (ref "U1") (pin "17/A3") (pinfunction "17/A3_17/A3") (pintype "bidirectional"))
      (node (ref "XTS") (pin "MP") (pinfunction "MP_MP") (pintype "passive"))
    )
    (net (code "34") (name "Net-(CON9D-K)") (class "Default")
      (node (ref "C15") (pin "1") (pinfunction "1_1") (pintype "passive"))
      (node (ref "CON9") (pin "4") (pinfunction "K_4") (pintype "passive"))
      (node (ref "PTC3") (pin "1") (pinfunction "1_1") (pintype "passive"))
      (node (ref "R60") (pin "2") (pinfunction "2_2") (pintype "passive"))
    )
    (net (code "35") (name "Net-(CON11-Pad1)") (class "Default")
      (node (ref "CON11") (pin "1") (pinfunction "1_1") (pintype "passive"))
      (node (ref "R10") (pin "2") (pinfunction "2_2") (pintype "passive"))
      (node (ref "TX1") (pin "MP") (pinfunction "MP_MP") (pintype "passive"))
      (node (ref "U1") (pin "1") (pinfunction "1_1") (pintype "bidirectional"))
    )
    (net (code "36") (name "Net-(CON11-Pad8)") (class "Default")
      (node (ref "CON11") (pin "8") (pinfunction "8_8") (pintype "passive"))
      (node (ref "R9") (pin "2") (pinfunction "2_2") (pintype "passive"))
      (node (ref "RX1") (pin "MP") (pinfunction "MP_MP") (pintype "passive"))
      (node (ref "U1") (pin "0") (pinfunction "0_0") (pintype "bidirectional"))
    )
    (net (code "37") (name "Net-(CONN10B-F)") (class "Default")
      (node (ref "CONN10") (pin "2") (pinfunction "F_2") (pintype "passive"))
      (node (ref "R48") (pin "2") (pinfunction "2_2") (pintype "passive"))
    )
    (net (code "38") (name "Net-(CONN10C-F)") (class "Default")
      (node (ref "CONN10") (pin "3") (pinfunction "F_3") (pintype "passive"))
      (node (ref "R51") (pin "2") (pinfunction "2_2") (pintype "passive"))
    )
    (net (code "39") (name "Net-(CONN10G-F)") (class "Default")
      (node (ref "CONN10") (pin "7") (pinfunction "F_7") (pintype "passive"))
      (node (ref "R49") (pin "2") (pinfunction "2_2") (pintype "passive"))
    )
    (net (code "40") (name "Net-(CONN10I-F)") (class "Default")
      (node (ref "CONN10") (pin "9") (pinfunction "F_9") (pintype "passive"))
      (node (ref "R50") (pin "2") (pinfunction "2_2") (pintype "passive"))
    )
    (net (code "41") (name "Net-(D2-PadC)") (class "Default")
      (node (ref "D2") (pin "C") (pinfunction "C_C") (pintype "passive"))
      (node (ref "PTC1") (pin "2") (pinfunction "2_2") (pintype "passive"))
    )
    (net (code "42") (name "Net-(D6-PadA)") (class "Default")
      (node (ref "D6") (pin "A") (pinfunction "A_A") (pintype "passive"))
      (node (ref "NTC2") (pin "1") (pinfunction "1_1") (pintype "passive"))
      (node (ref "R38") (pin "2") (pinfunction "2_2") (pintype "passive"))
    )
    (net (code "43") (name "Net-(D7-ANODE1)") (class "Default")
      (node (ref "D2") (pin "A") (pinfunction "A_A") (pintype "passive"))
      (node (ref "D7") (pin "GATE") (pinfunction "ANODE1_GATE") (pintype "passive"))
      (node (ref "D7") (pin "SOURCE") (pinfunction "ANODE2_SOURCE") (pintype "passive"))
      (node (ref "VREG1") (pin "14") (pinfunction "+VOUT_14") (pintype "input"))
    )
    (net (code "44") (name "Net-(F1-1A)") (class "Default")
      (node (ref "F1") (pin "P$1") (pinfunction "1A_P$1") (pintype "passive"))
      (node (ref "NTC2") (pin "2") (pinfunction "2_2") (pintype "passive"))
    )
    (net (code "45") (name "Net-(IC1-ADJ)") (class "Default")
      (node (ref "C5") (pin "1") (pinfunction "1_1") (pintype "passive"))
      (node (ref "IC1") (pin "4") (pinfunction "ADJ_4") (pintype "passive"))
      (node (ref "R46") (pin "1") (pinfunction "1_1") (pintype "passive"))
    )
    (net (code "46") (name "Net-(IC1-OUT)") (class "Default")
      (node (ref "+3.7V") (pin "MP") (pinfunction "MP_MP") (pintype "passive"))
      (node (ref "C12") (pin "1") (pinfunction "1_1") (pintype "passive"))
      (node (ref "C14") (pin "1") (pinfunction "1_1") (pintype "passive"))
      (node (ref "D5") (pin "A") (pinfunction "A_A") (pintype "passive"))
      (node (ref "IC1") (pin "5") (pinfunction "OUT_5") (pintype "output"))
      (node (ref "R46") (pin "2") (pinfunction "2_2") (pintype "passive"))
    )
    (net (code "47") (name "Net-(IC2A-+IN)") (class "Default")
      (node (ref "C23") (pin "1") (pinfunction "1_1") (pintype "passive"))
      (node (ref "IC2") (pin "3") (pinfunction "+IN_3") (pintype "input"))
      (node (ref "R30") (pin "1") (pinfunction "1_1") (pintype "passive"))
    )
    (net (code "48") (name "Net-(IC2A--IN)") (class "Default")
      (node (ref "IC2") (pin "2") (pinfunction "-IN_2") (pintype "input"))
      (node (ref "R34") (pin "1") (pinfunction "1_1") (pintype "passive"))
      (node (ref "R41") (pin "1") (pinfunction "1_1") (pintype "passive"))
    )
    (net (code "49") (name "Net-(IC2A-OUT)") (class "Default")
      (node (ref "IC2") (pin "1") (pinfunction "OUT_1") (pintype "output"))
      (node (ref "R41") (pin "2") (pinfunction "2_2") (pintype "passive"))
      (node (ref "R53") (pin "1") (pinfunction "1_1") (pintype "passive"))
    )
    (net (code "50") (name "Net-(IC2B-+IN)") (class "Default")
      (node (ref "C24") (pin "1") (pinfunction "1_1") (pintype "passive"))
      (node (ref "IC2") (pin "5") (pinfunction "+IN_5") (pintype "input"))
      (node (ref "R31") (pin "1") (pinfunction "1_1") (pintype "passive"))
    )
    (net (code "51") (name "Net-(IC2B--IN)") (class "Default")
      (node (ref "IC2") (pin "6") (pinfunction "-IN_6") (pintype "input"))
      (node (ref "R35") (pin "1") (pinfunction "1_1") (pintype "passive"))
      (node (ref "R42") (pin "1") (pinfunction "1_1") (pintype "passive"))
    )
    (net (code "52") (name "Net-(IC2B-OUT)") (class "Default")
      (node (ref "IC2") (pin "7") (pinfunction "OUT_7") (pintype "output"))
      (node (ref "R42") (pin "2") (pinfunction "2_2") (pintype "passive"))
      (node (ref "R54") (pin "1") (pinfunction "1_1") (pintype "passive"))
    )
    (net (code "53") (name "Net-(IC2C-+IN)") (class "Default")
      (node (ref "IC2") (pin "10") (pinfunction "+IN_10") (pintype "input"))
      (node (ref "IC2") (pin "12") (pinfunction "+IN_12") (pintype "input"))
      (node (ref "R24") (pin "2") (pinfunction "2_2") (pintype "passive"))
    )
    (net (code "54") (name "Net-(IC2C--IN)") (class "Default")
      (node (ref "IC2") (pin "8") (pinfunction "OUT_8") (pintype "output"))
      (node (ref "IC2") (pin "9") (pinfunction "-IN_9") (pintype "input"))
    )
    (net (code "55") (name "Net-(IC2D--IN)") (class "Default")
      (node (ref "IC2") (pin "13") (pinfunction "-IN_13") (pintype "input"))
      (node (ref "IC2") (pin "14") (pinfunction "OUT_14") (pintype "output"))
    )
    (net (code "56") (name "Net-(IC3-+IN)") (class "Default")
      (node (ref "C41") (pin "2") (pinfunction "2_2") (pintype "passive"))
      (node (ref "IC3") (pin "3") (pinfunction "+IN_3") (pintype "input"))
      (node (ref "RN1") (pin "7") (pinfunction "7_7") (pintype "passive"))
      (node (ref "RN1") (pin "8") (pinfunction "8_8") (pintype "passive"))
    )
    (net (code "57") (name "Net-(IC3--IN)") (class "Default")
      (node (ref "C42") (pin "2") (pinfunction "2_2") (pintype "passive"))
      (node (ref "IC3") (pin "4") (pinfunction "-IN_4") (pintype "input"))
      (node (ref "RN1") (pin "5") (pinfunction "5_5") (pintype "passive"))
      (node (ref "RN1") (pin "6") (pinfunction "6_6") (pintype "passive"))
    )
    (net (code "58") (name "Net-(IC4-IN)") (class "Default")
      (node (ref "C18") (pin "1") (pinfunction "1_1") (pintype "passive"))
      (node (ref "IC4") (pin "1") (pinfunction "IN_1") (pintype "input"))
      (node (ref "L1") (pin "1") (pinfunction "1_1") (pintype "passive"))
    )
    (net (code "59") (name "Net-(IC5-CANH)") (class "Default")
      (node (ref "IC5") (pin "7") (pinfunction "CANH_7") (pintype "input"))
      (node (ref "R49") (pin "1") (pinfunction "1_1") (pintype "passive"))
      (node (ref "R52") (pin "2") (pinfunction "2_2") (pintype "passive"))
    )
    (net (code "60") (name "Net-(IC5-CANL)") (class "Default")
      (node (ref "IC5") (pin "6") (pinfunction "CANL_6") (pintype "input"))
      (node (ref "R48") (pin "1") (pinfunction "1_1") (pintype "passive"))
      (node (ref "R55") (pin "2") (pinfunction "2_2") (pintype "passive"))
    )
    (net (code "61") (name "Net-(IC5-GND2)") (class "Default")
      (node (ref "C46") (pin "1") (pinfunction "1_1") (pintype "passive"))
      (node (ref "IC5") (pin "5") (pinfunction "GND2_5") (pintype "input"))
      (node (ref "R47") (pin "1") (pinfunction "1_1") (pintype "passive"))
      (node (ref "R51") (pin "1") (pinfunction "1_1") (pintype "passive"))
    )
    (net (code "62") (name "Net-(IC6-ADJ)") (class "Default")
      (node (ref "C48") (pin "1") (pinfunction "1_1") (pintype "passive"))
      (node (ref "IC6") (pin "4") (pinfunction "ADJ_4") (pintype "passive"))
    )
    (net (code "63") (name "Net-(IC6-OUT)") (class "Default")
      (node (ref "C49") (pin "1") (pinfunction "1_1") (pintype "passive"))
      (node (ref "C50") (pin "1") (pinfunction "1_1") (pintype "passive"))
      (node (ref "CON11") (pin "7") (pinfunction "7_7") (pintype "passive"))
      (node (ref "IC6") (pin "5") (pinfunction "OUT_5") (pintype "output"))
    )
    (net (code "64") (name "Net-(K1-PadNO)") (class "Default")
      (node (ref "K1") (pin "NO") (pinfunction "NO_NO") (pintype "passive"))
      (node (ref "TB1") (pin "3") (pinfunction "3_3") (pintype "passive"))
    )
    (net (code "65") (name "Net-(K2-PadNO)") (class "Default")
      (node (ref "K2") (pin "NO") (pinfunction "NO_NO") (pintype "passive"))
      (node (ref "TB2") (pin "3") (pinfunction "3_3") (pintype "passive"))
    )
    (net (code "66") (name "Net-(L/TBD-PadMP)") (class "Default")
      (node (ref "L/TBD") (pin "MP") (pinfunction "MP_MP") (pintype "passive"))
      (node (ref "R57") (pin "2") (pinfunction "2_2") (pintype "passive"))
      (node (ref "U1") (pin "18/A4") (pinfunction "18/A4_18/A4") (pintype "bidirectional"))
    )
    (net (code "67") (name "Net-(LD1-PadC)") (class "Default")
      (node (ref "LD1") (pin "C") (pinfunction "C_C") (pintype "passive"))
      (node (ref "R11") (pin "1") (pinfunction "1_1") (pintype "passive"))
    )
    (net (code "68") (name "Net-(LD2-AG)") (class "Default")
      (node (ref "LD2") (pin "AX") (pinfunction "AG_AX") (pintype "passive"))
      (node (ref "U1") (pin "8") (pinfunction "8_8") (pintype "bidirectional"))
    )
    (net (code "69") (name "Net-(LD2-PadAR)") (class "Default")
      (node (ref "LD2") (pin "AR") (pinfunction "AR_AR") (pintype "passive"))
      (node (ref "U1") (pin "7") (pinfunction "7_7") (pintype "bidirectional"))
    )
    (net (code "70") (name "Net-(LD2-PadC)") (class "Default")
      (node (ref "LD2") (pin "C") (pinfunction "C_C") (pintype "passive"))
      (node (ref "R13") (pin "1") (pinfunction "1_1") (pintype "passive"))
    )
    (net (code "71") (name "Net-(LED1-A)") (class "Default")
      (node (ref "LED1") (pin "ANODE") (pinfunction "A_ANODE") (pintype "passive"))
      (node (ref "R28") (pin "1") (pinfunction "1_1") (pintype "passive"))
    )
    (net (code "72") (name "Net-(LED2-C)") (class "Default")
      (node (ref "LED2") (pin "CATHODE") (pinfunction "C_CATHODE") (pintype "passive"))
      (node (ref "R6") (pin "1") (pinfunction "1_1") (pintype "passive"))
    )
    (net (code "73") (name "Net-(LED3-A)") (class "Default")
      (node (ref "LED3") (pin "ANODE") (pinfunction "A_ANODE") (pintype "passive"))
      (node (ref "R43") (pin "1") (pinfunction "1_1") (pintype "passive"))
    )
    (net (code "74") (name "Net-(LED4-C)") (class "Default")
      (node (ref "LED4") (pin "CATHODE") (pinfunction "C_CATHODE") (pintype "passive"))
      (node (ref "R8") (pin "1") (pinfunction "1_1") (pintype "passive"))
    )
    (net (code "75") (name "Net-(LED5-C)") (class "Default")
      (node (ref "LED5") (pin "CATHODE") (pinfunction "C_CATHODE") (pintype "passive"))
      (node (ref "R44") (pin "2") (pinfunction "2_2") (pintype "passive"))
    )
    (net (code "76") (name "Net-(LED6-C)") (class "Default")
      (node (ref "LED6") (pin "CATHODE") (pinfunction "C_CATHODE") (pintype "passive"))
      (node (ref "R45") (pin "1") (pinfunction "1_1") (pintype "passive"))
    )
    (net (code "77") (name "Net-(LED7-C)") (class "Default")
      (node (ref "LED7") (pin "CATHODE") (pinfunction "C_CATHODE") (pintype "passive"))
      (node (ref "R19") (pin "1") (pinfunction "1_1") (pintype "passive"))
    )
    (net (code "78") (name "Net-(LED8-A)") (class "Default")
      (node (ref "LED8") (pin "ANODE") (pinfunction "A_ANODE") (pintype "passive"))
      (node (ref "R58") (pin "1") (pinfunction "1_1") (pintype "passive"))
    )
    (net (code "79") (name "Net-(LED9-A)") (class "Default")
      (node (ref "LED9") (pin "ANODE") (pinfunction "A_ANODE") (pintype "passive"))
      (node (ref "R60") (pin "1") (pinfunction "1_1") (pintype "passive"))
    )
    (net (code "80") (name "Net-(OPTO1-A)") (class "Default")
      (node (ref "C36") (pin "1") (pinfunction "1_1") (pintype "passive"))
      (node (ref "OPTO1") (pin "1") (pinfunction "A_1") (pintype "passive"))
      (node (ref "R20") (pin "1") (pinfunction "1_1") (pintype "passive"))
    )
    (net (code "81") (name "Net-(OPTO1-C)") (class "Default")
      (node (ref "C36") (pin "2") (pinfunction "2_2") (pintype "passive"))
      (node (ref "CON4") (pin "1") (pinfunction "1_1") (pintype "passive"))
      (node (ref "OPTO1") (pin "2") (pinfunction "C_2") (pintype "passive"))
      (node (ref "R17") (pin "1") (pinfunction "1_1") (pintype "passive"))
      (node (ref "Z2") (pin "1") (pinfunction "A_1") (pintype "passive"))
    )
    (net (code "82") (name "Net-(OPTO2-A)") (class "Default")
      (node (ref "C35") (pin "1") (pinfunction "1_1") (pintype "passive"))
      (node (ref "OPTO2") (pin "1") (pinfunction "A_1") (pintype "passive"))
      (node (ref "R33") (pin "1") (pinfunction "1_1") (pintype "passive"))
    )
    (net (code "83") (name "Net-(OPTO2-C)") (class "Default")
      (node (ref "C35") (pin "2") (pinfunction "2_2") (pintype "passive"))
      (node (ref "CON6") (pin "1") (pinfunction "1_1") (pintype "passive"))
      (node (ref "OPTO2") (pin "2") (pinfunction "C_2") (pintype "passive"))
      (node (ref "R37") (pin "1") (pinfunction "1_1") (pintype "passive"))
      (node (ref "Z3") (pin "1") (pinfunction "A_1") (pintype "passive"))
    )
    (net (code "84") (name "Net-(OPTO3-A)") (class "Default")
      (node (ref "OPTO3") (pin "1") (pinfunction "A_1") (pintype "passive"))
      (node (ref "R57") (pin "1") (pinfunction "1_1") (pintype "passive"))
    )
    (net (code "85") (name "Net-(OPTO3-COL)") (class "Default")
      (node (ref "OPTO3") (pin "4") (pinfunction "COL_4") (pintype "passive"))
      (node (ref "PTC2") (pin "2") (pinfunction "2_2") (pintype "passive"))
    )
    (net (code "86") (name "Net-(OPTO4-A)") (class "Default")
      (node (ref "OPTO4") (pin "1") (pinfunction "A_1") (pintype "passive"))
      (node (ref "R59") (pin "1") (pinfunction "1_1") (pintype "passive"))
    )
    (net (code "87") (name "Net-(OPTO4-COL)") (class "Default")
      (node (ref "OPTO4") (pin "4") (pinfunction "COL_4") (pintype "passive"))
      (node (ref "PTC3") (pin "2") (pinfunction "2_2") (pintype "passive"))
    )
    (net (code "88") (name "Net-(Q1-G)") (class "Default")
      (node (ref "Q1") (pin "1") (pinfunction "G_1") (pintype "passive"))
      (node (ref "R7") (pin "1") (pinfunction "1_1") (pintype "passive"))
    )
    (net (code "89") (name "Net-(Q1-S)") (class "Default")
      (node (ref "Q1") (pin "2") (pinfunction "S_2") (pintype "passive"))
      (node (ref "R1") (pin "1") (pinfunction "1_1") (pintype "passive"))
      (node (ref "R5") (pin "2") (pinfunction "2_2") (pintype "passive"))
    )
    (net (code "90") (name "Net-(Q3-D)") (class "Default")
      (node (ref "D1") (pin "A") (pinfunction "A_A") (pintype "passive"))
      (node (ref "K1") (pin "V-") (pinfunction "V-_V-") (pintype "passive"))
      (node (ref "Q3") (pin "3") (pinfunction "D_3") (pintype "passive"))
      (node (ref "R6") (pin "2") (pinfunction "2_2") (pintype "passive"))
    )
    (net (code "91") (name "Net-(Q3-G)") (class "Default")
      (node (ref "Q3") (pin "1") (pinfunction "G_1") (pintype "passive"))
      (node (ref "R3") (pin "1") (pinfunction "1_1") (pintype "passive"))
    )
    (net (code "92") (name "Net-(Q4-D)") (class "Default")
      (node (ref "D4") (pin "A") (pinfunction "A_A") (pintype "passive"))
      (node (ref "K2") (pin "V-") (pinfunction "V-_V-") (pintype "passive"))
      (node (ref "Q4") (pin "3") (pinfunction "D_3") (pintype "passive"))
      (node (ref "R8") (pin "2") (pinfunction "2_2") (pintype "passive"))
    )
    (net (code "93") (name "Net-(Q4-G)") (class "Default")
      (node (ref "Q4") (pin "1") (pinfunction "G_1") (pintype "passive"))
      (node (ref "R4") (pin "1") (pinfunction "1_1") (pintype "passive"))
    )
    (net (code "94") (name "Net-(R12-Pad1)") (class "Default")
      (node (ref "R12") (pin "1") (pinfunction "1_1") (pintype "passive"))
      (node (ref "S1") (pin "1") (pinfunction "1_1") (pintype "passive"))
      (node (ref "S1") (pin "2") (pinfunction "2_2") (pintype "passive"))
    )
    (net (code "95") (name "Net-(R12-Pad2)") (class "Default")
      (node (ref "R12") (pin "2") (pinfunction "2_2") (pintype "passive"))
      (node (ref "R59") (pin "2") (pinfunction "2_2") (pintype "passive"))
      (node (ref "TP-SW/FAN") (pin "MP") (pinfunction "MP_MP") (pintype "passive"))
      (node (ref "U1") (pin "2") (pinfunction "2_2") (pintype "bidirectional"))
    )
    (net (code "96") (name "Net-(R14-Pad2)") (class "Default")
      (node (ref "R14") (pin "2") (pinfunction "2_2") (pintype "passive"))
      (node (ref "R15") (pin "1") (pinfunction "1_1") (pintype "passive"))
      (node (ref "U1") (pin "A10") (pinfunction "A10_A10") (pintype "input"))
      (node (ref "VBAL/2") (pin "MP") (pinfunction "MP_MP") (pintype "passive"))
    )
    (net (code "97") (name "Net-(R38-Pad1)") (class "Default")
      (node (ref "R38") (pin "1") (pinfunction "1_1") (pintype "passive"))
      (node (ref "R39") (pin "2") (pinfunction "2_2") (pintype "passive"))
    )
    (net (code "98") (name "Net-(R39-Pad1)") (class "Default")
      (node (ref "R39") (pin "1") (pinfunction "1_1") (pintype "passive"))
      (node (ref "R40") (pin "2") (pinfunction "2_2") (pintype "passive"))
    )
    (net (code "99") (name "Net-(TB1A-3)") (class "Default")
      (node (ref "K1") (pin "COM") (pinfunction "COM_COM") (pintype "passive"))
      (node (ref "TB1") (pin "1") (pinfunction "3_1") (pintype "passive"))
    )
    (net (code "100") (name "Net-(TB1B-3)") (class "Default")
      (node (ref "K1") (pin "NC") (pinfunction "NC_NC") (pintype "passive"))
      (node (ref "TB1") (pin "2") (pinfunction "3_2") (pintype "passive"))
    )
    (net (code "101") (name "Net-(TB2A-3)") (class "Default")
      (node (ref "K2") (pin "COM") (pinfunction "COM_COM") (pintype "passive"))
      (node (ref "TB2") (pin "1") (pinfunction "3_1") (pintype "passive"))
    )
    (net (code "102") (name "Net-(TB2B-3)") (class "Default")
      (node (ref "K2") (pin "NC") (pinfunction "NC_NC") (pintype "passive"))
      (node (ref "TB2") (pin "2") (pinfunction "3_2") (pintype "passive"))
    )
    (net (code "103") (name "Net-(U1-DAC)") (class "Default")
      (node (ref "R22") (pin "2") (pinfunction "2_2") (pintype "passive"))
      (node (ref "U1") (pin "14") (pinfunction "DAC_14") (pintype "output"))
    )
    (net (code "104") (name "Net-(U3-+INA)") (class "Default")
      (node (ref "C28") (pin "1") (pinfunction "1_1") (pintype "passive"))
      (node (ref "R18") (pin "2") (pinfunction "2_2") (pintype "passive"))
      (node (ref "R22") (pin "1") (pinfunction "1_1") (pintype "passive"))
      (node (ref "U3") (pin "3") (pinfunction "+INA_3") (pintype "input"))
    )
    (net (code "105") (name "Net-(U3--INA)") (class "Default")
      (node (ref "C33") (pin "2") (pinfunction "2_2") (pintype "passive"))
      (node (ref "R5") (pin "1") (pinfunction "1_1") (pintype "passive"))
      (node (ref "U3") (pin "2") (pinfunction "-INA_2") (pintype "input"))
    )
    (net (code "106") (name "Net-(U3--INB)") (class "Default")
      (node (ref "U3") (pin "6") (pinfunction "-INB_6") (pintype "input"))
      (node (ref "U3") (pin "7") (pinfunction "OUTB_7") (pintype "output"))
    )
    (net (code "107") (name "Net-(U3-OUTA)") (class "Default")
      (node (ref "C33") (pin "1") (pinfunction "1_1") (pintype "passive"))
      (node (ref "R7") (pin "2") (pinfunction "2_2") (pintype "passive"))
      (node (ref "U3") (pin "1") (pinfunction "OUTA_1") (pintype "output"))
    )
    (net (code "108") (name "Net-(U4-VIN+)") (class "Default")
      (node (ref "C8") (pin "1") (pinfunction "1_1") (pintype "passive"))
      (node (ref "R2") (pin "2") (pinfunction "2_2") (pintype "passive"))
      (node (ref "R40") (pin "1") (pinfunction "1_1") (pintype "passive"))
      (node (ref "U4") (pin "2") (pinfunction "VIN+_2") (pintype "input"))
    )
    (net (code "109") (name "Net-(U4-VOUT+)") (class "Default")
      (node (ref "RN1") (pin "2") (pinfunction "2_2") (pintype "passive"))
      (node (ref "U4") (pin "7") (pinfunction "VOUT+_7") (pintype "output"))
    )
    (net (code "110") (name "Net-(U4-VOUT-)") (class "Default")
      (node (ref "RN1") (pin "3") (pinfunction "3_3") (pintype "passive"))
      (node (ref "U4") (pin "6") (pinfunction "VOUT-_6") (pintype "output"))
    )
    (net (code "111") (name "Net-(VREG1-+VIN)") (class "Default")
      (node (ref "C13") (pin "+") (pinfunction "+_+") (pintype "passive"))
      (node (ref "C22") (pin "1") (pinfunction "1_1") (pintype "passive"))
      (node (ref "C26") (pin "1") (pinfunction "1_1") (pintype "passive"))
      (node (ref "C27") (pin "1") (pinfunction "1_1") (pintype "passive"))
      (node (ref "C34") (pin "+") (pinfunction "+_+") (pintype "passive"))
      (node (ref "D6") (pin "C") (pinfunction "C_C") (pintype "passive"))
      (node (ref "VREG1") (pin "22") (pinfunction "+VIN._22") (pintype "input"))
      (node (ref "VREG1") (pin "23") (pinfunction "+VIN_23") (pintype "input"))
      (node (ref "Z1") (pin "C") (pinfunction "C_C") (pintype "passive"))
    )
    (net (code "112") (name "Net-(VREG1-ON{slash}OFF)") (class "Default")
      (node (ref "TP-EN1") (pin "MP") (pinfunction "MP_MP") (pintype "passive"))
      (node (ref "VREG1") (pin "1") (pinfunction "ON/OFF_1") (pintype "input"))
    )
    (net (code "113") (name "Net-(Z2-C)") (class "Default")
      (node (ref "R17") (pin "2") (pinfunction "2_2") (pintype "passive"))
      (node (ref "R20") (pin "2") (pinfunction "2_2") (pintype "passive"))
      (node (ref "R29") (pin "1") (pinfunction "1_1") (pintype "passive"))
      (node (ref "Z2") (pin "3") (pinfunction "C_3") (pintype "passive"))
    )
    (net (code "114") (name "Net-(Z3-C)") (class "Default")
      (node (ref "R32") (pin "1") (pinfunction "1_1") (pintype "passive"))
      (node (ref "R33") (pin "2") (pinfunction "2_2") (pintype "passive"))
      (node (ref "R37") (pin "2") (pinfunction "2_2") (pintype "passive"))
      (node (ref "Z3") (pin "3") (pinfunction "C_3") (pintype "passive"))
    )
    (net (code "115") (name "PACKGND") (class "Default")
      (node (ref "C13") (pin "-") (pinfunction "-_-") (pintype "passive"))
      (node (ref "C22") (pin "2") (pinfunction "2_2") (pintype "passive"))
      (node (ref "C26") (pin "2") (pinfunction "2_2") (pintype "passive"))
      (node (ref "C27") (pin "2") (pinfunction "2_2") (pintype "passive"))
      (node (ref "C34") (pin "-") (pinfunction "-_-") (pintype "passive"))
      (node (ref "C37") (pin "2") (pinfunction "2_2") (pintype "passive"))
      (node (ref "C39") (pin "2") (pinfunction "2_2") (pintype "passive"))
      (node (ref "C45") (pin "2") (pinfunction "2_2") (pintype "passive"))
      (node (ref "C8") (pin "2") (pinfunction "2_2") (pintype "passive"))
      (node (ref "CON2") (pin "3") (pinfunction "3_3") (pintype "passive"))
      (node (ref "R2") (pin "1") (pinfunction "1_1") (pintype "passive"))
      (node (ref "U4") (pin "3") (pinfunction "SHDN_3") (pintype "input"))
      (node (ref "U4") (pin "4") (pinfunction "GND1_4") (pintype "power_in"))
      (node (ref "VREG1") (pin "2") (pinfunction "-VIN_2") (pintype "input"))
      (node (ref "VREG1") (pin "3") (pinfunction "-VIN._3") (pintype "input"))
      (node (ref "VREG2") (pin "4") (pinfunction "-VOUT_4") (pintype "passive"))
      (node (ref "Z1") (pin "A") (pinfunction "A_A") (pintype "passive"))
    )
    (net (code "116") (name "PWM1") (class "Default")
      (node (ref "R26") (pin "2") (pinfunction "2_2") (pintype "passive"))
      (node (ref "TP1") (pin "MP") (pinfunction "MP_MP") (pintype "passive"))
      (node (ref "U1") (pin "20/A6") (pinfunction "20/A6_20/A6") (pintype "bidirectional"))
    )
    (net (code "117") (name "PWM2") (class "Default")
      (node (ref "R27") (pin "2") (pinfunction "2_2") (pintype "passive"))
      (node (ref "TP3") (pin "MP") (pinfunction "MP_MP") (pintype "passive"))
      (node (ref "U1") (pin "21/A7") (pinfunction "21/A7_21/A7") (pintype "bidirectional"))
    )
    (net (code "118") (name "RELAYDR1") (class "Default")
      (node (ref "R3") (pin "2") (pinfunction "2_2") (pintype "passive"))
      (node (ref "TP-REL1") (pin "MP") (pinfunction "MP_MP") (pintype "passive"))
      (node (ref "U1") (pin "5") (pinfunction "5_5") (pintype "bidirectional"))
    )
    (net (code "119") (name "RELAYDR2") (class "Default")
      (node (ref "R4") (pin "2") (pinfunction "2_2") (pintype "passive"))
      (node (ref "U1") (pin "6") (pinfunction "6_6") (pintype "bidirectional"))
    )
    (net (code "120") (name "RX-CAN") (class "Default")
      (node (ref "IC5") (pin "2") (pinfunction "RXD_2") (pintype "input"))
      (node (ref "U1") (pin "4") (pinfunction "4_4") (pintype "bidirectional"))
    )
    (net (code "121") (name "TX-CAN") (class "Default")
      (node (ref "IC5") (pin "3") (pinfunction "TXD_3") (pintype "input"))
      (node (ref "U1") (pin "3") (pinfunction "3_3") (pintype "bidirectional"))
    )
    (net (code "122") (name "VPACK") (class "Default")
      (node (ref "CON2") (pin "1") (pinfunction "1_1") (pintype "passive"))
      (node (ref "F1") (pin "P$2") (pinfunction "2A_P$2") (pintype "passive"))
    )
    (net (code "123") (name "VSCALED-PACK") (class "Default")
      (node (ref "C42") (pin "1") (pinfunction "1_1") (pintype "passive"))
      (node (ref "C7") (pin "1") (pinfunction "1_1") (pintype "passive"))
      (node (ref "IC3") (pin "1") (pinfunction "OUT_1") (pintype "output"))
      (node (ref "RN1") (pin "4") (pinfunction "4_4") (pintype "passive"))
      (node (ref "U1") (pin "14/A0") (pinfunction "14/A0_14/A0") (pintype "bidirectional"))
    )
    (net (code "124") (name "unconnected-(CON11-Pad3)") (class "Default")
      (node (ref "CON11") (pin "3") (pinfunction "3_3") (pintype "passive"))
    )
    (net (code "125") (name "unconnected-(CON11-Pad4)") (class "Default")
      (node (ref "CON11") (pin "4") (pinfunction "4_4") (pintype "passive"))
    )
    (net (code "126") (name "unconnected-(CON11-Pad5)") (class "Default")
      (node (ref "CON11") (pin "5") (pinfunction "5_5") (pintype "passive"))
    )
    (net (code "127") (name "unconnected-(CON11-Pad6)") (class "Default")
      (node (ref "CON11") (pin "6") (pinfunction "6_6") (pintype "passive"))
    )
    (net (code "128") (name "unconnected-(CONN10A-F-Pad1)") (class "Default")
      (node (ref "CONN10") (pin "1") (pinfunction "F_1") (pintype "passive"))
    )
    (net (code "129") (name "unconnected-(CONN10D-F-Pad4)") (class "Default")
      (node (ref "CONN10") (pin "4") (pinfunction "F_4") (pintype "passive"))
    )
    (net (code "130") (name "unconnected-(CONN10E-F-Pad5)") (class "Default")
      (node (ref "CONN10") (pin "5") (pinfunction "F_5") (pintype "passive"))
    )
    (net (code "131") (name "unconnected-(CONN10F-F-Pad6)") (class "Default")
      (node (ref "CONN10") (pin "6") (pinfunction "F_6") (pintype "passive"))
    )
    (net (code "132") (name "unconnected-(CONN10H-F-Pad8)") (class "Default")
      (node (ref "CONN10") (pin "8") (pinfunction "F_8") (pintype "passive"))
    )
    (net (code "133") (name "unconnected-(FID1-PadTP)") (class "Default")
      (node (ref "FID1") (pin "TP") (pinfunction "TP_TP") (pintype "input"))
    )
    (net (code "134") (name "unconnected-(FID2-PadTP)") (class "Default")
      (node (ref "FID2") (pin "TP") (pinfunction "TP_TP") (pintype "input"))
    )
    (net (code "135") (name "unconnected-(FID3-PadTP)") (class "Default")
      (node (ref "FID3") (pin "TP") (pinfunction "TP_TP") (pintype "input"))
    )
    (net (code "136") (name "unconnected-(FID4-PadTP)") (class "Default")
      (node (ref "FID4") (pin "TP") (pinfunction "TP_TP") (pintype "input"))
    )
    (net (code "137") (name "unconnected-(VREG1-NC-Pad11)") (class "Default")
      (node (ref "VREG1") (pin "11") (pinfunction "NC_11") (pintype "input"))
    )
    (net (code "138") (name "unconnected-(VREG1-NOPIN-Pad9)") (class "Default")
      (node (ref "VREG1") (pin "9") (pinfunction "NOPIN_9") (pintype "input"))
    )
  )
)
